# AuxTalon.net
KiCad netlist of a schematic drawn in EAGLE
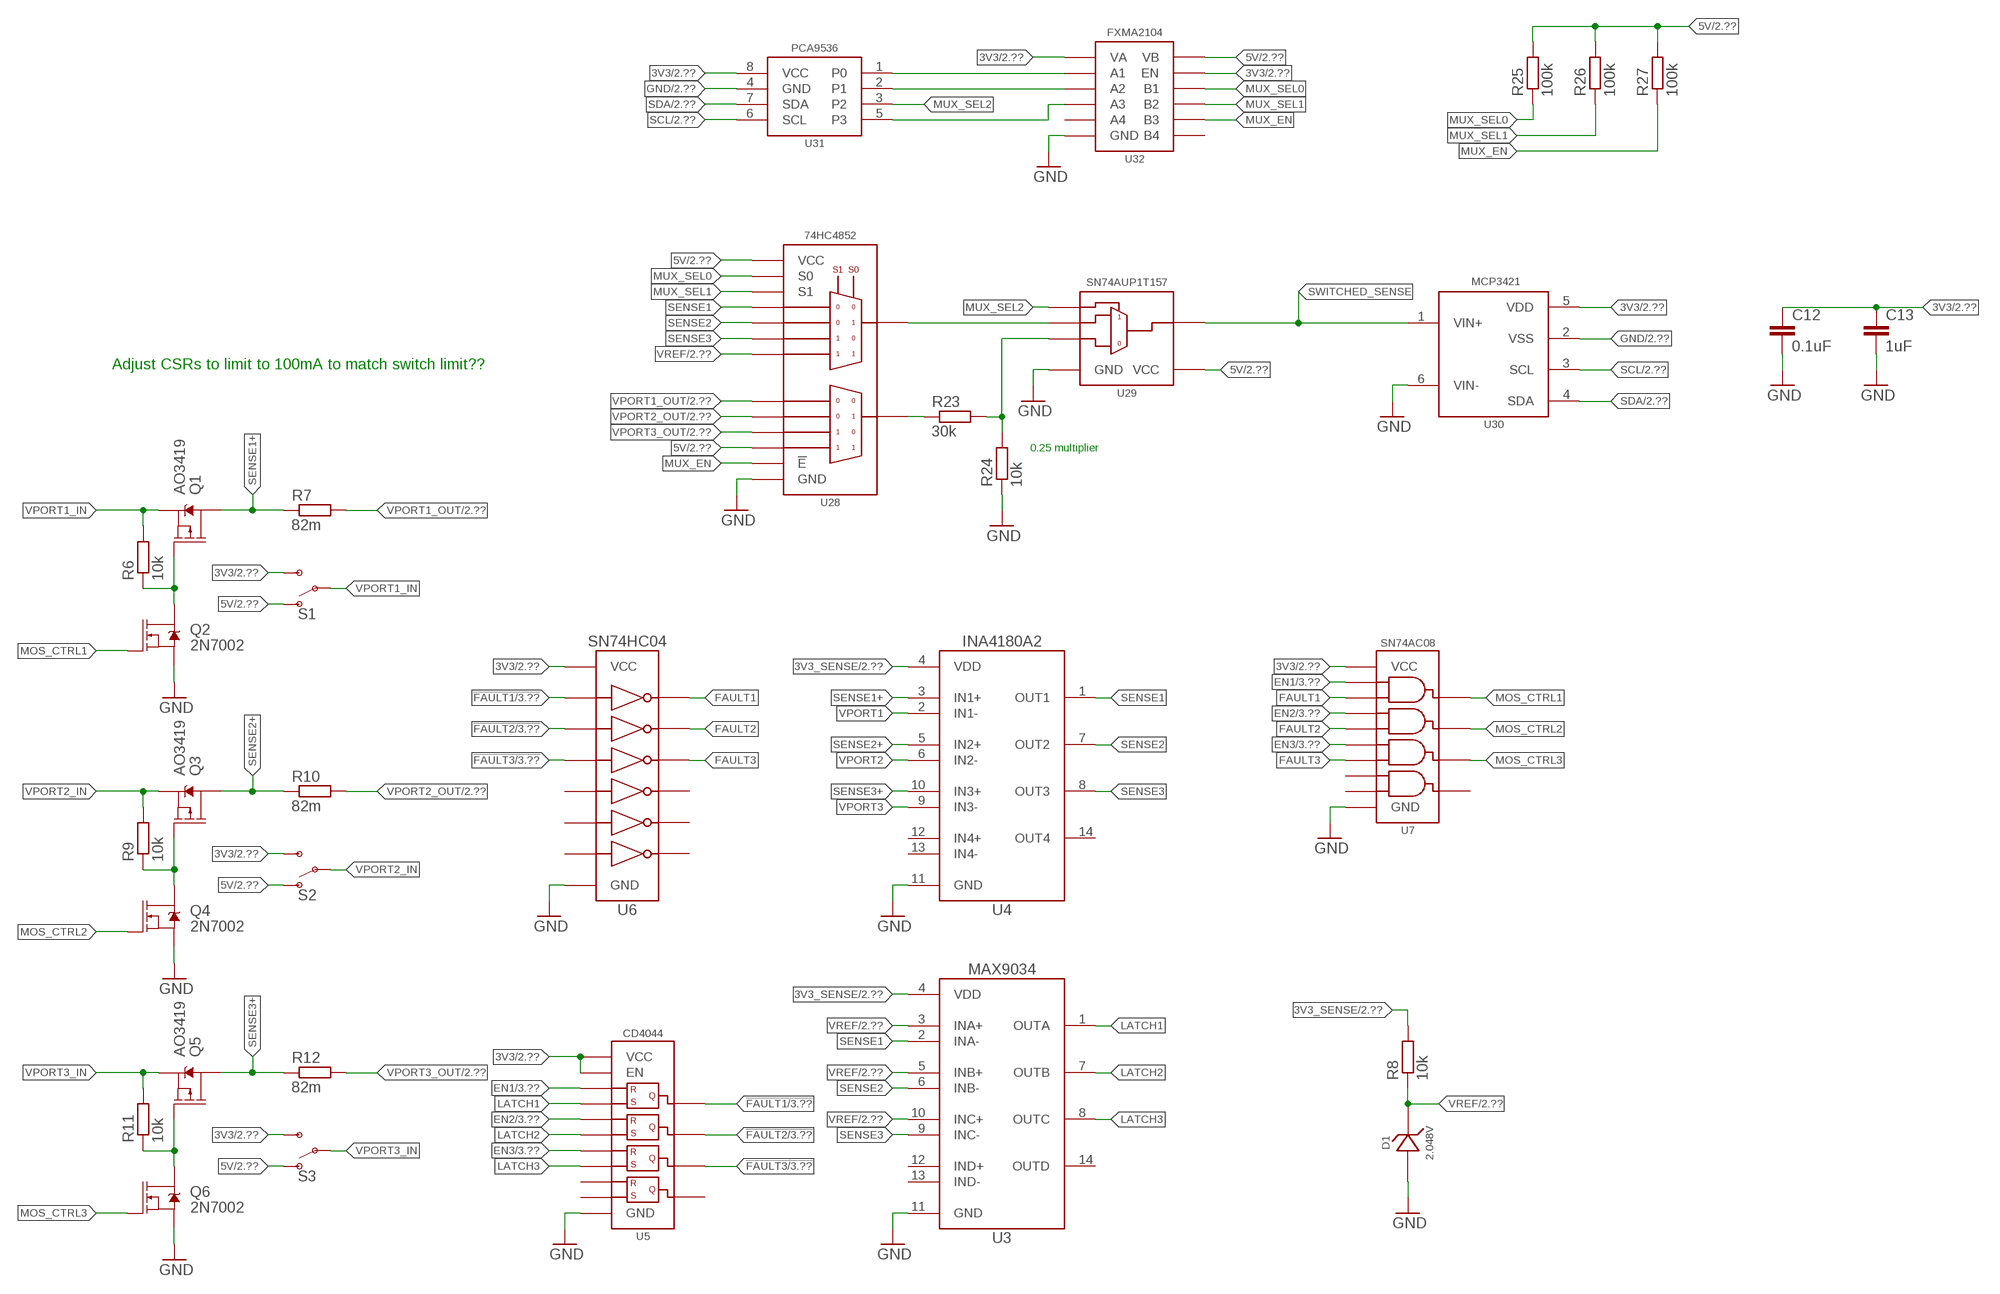
[diagram p0: schematic, sheet 1]
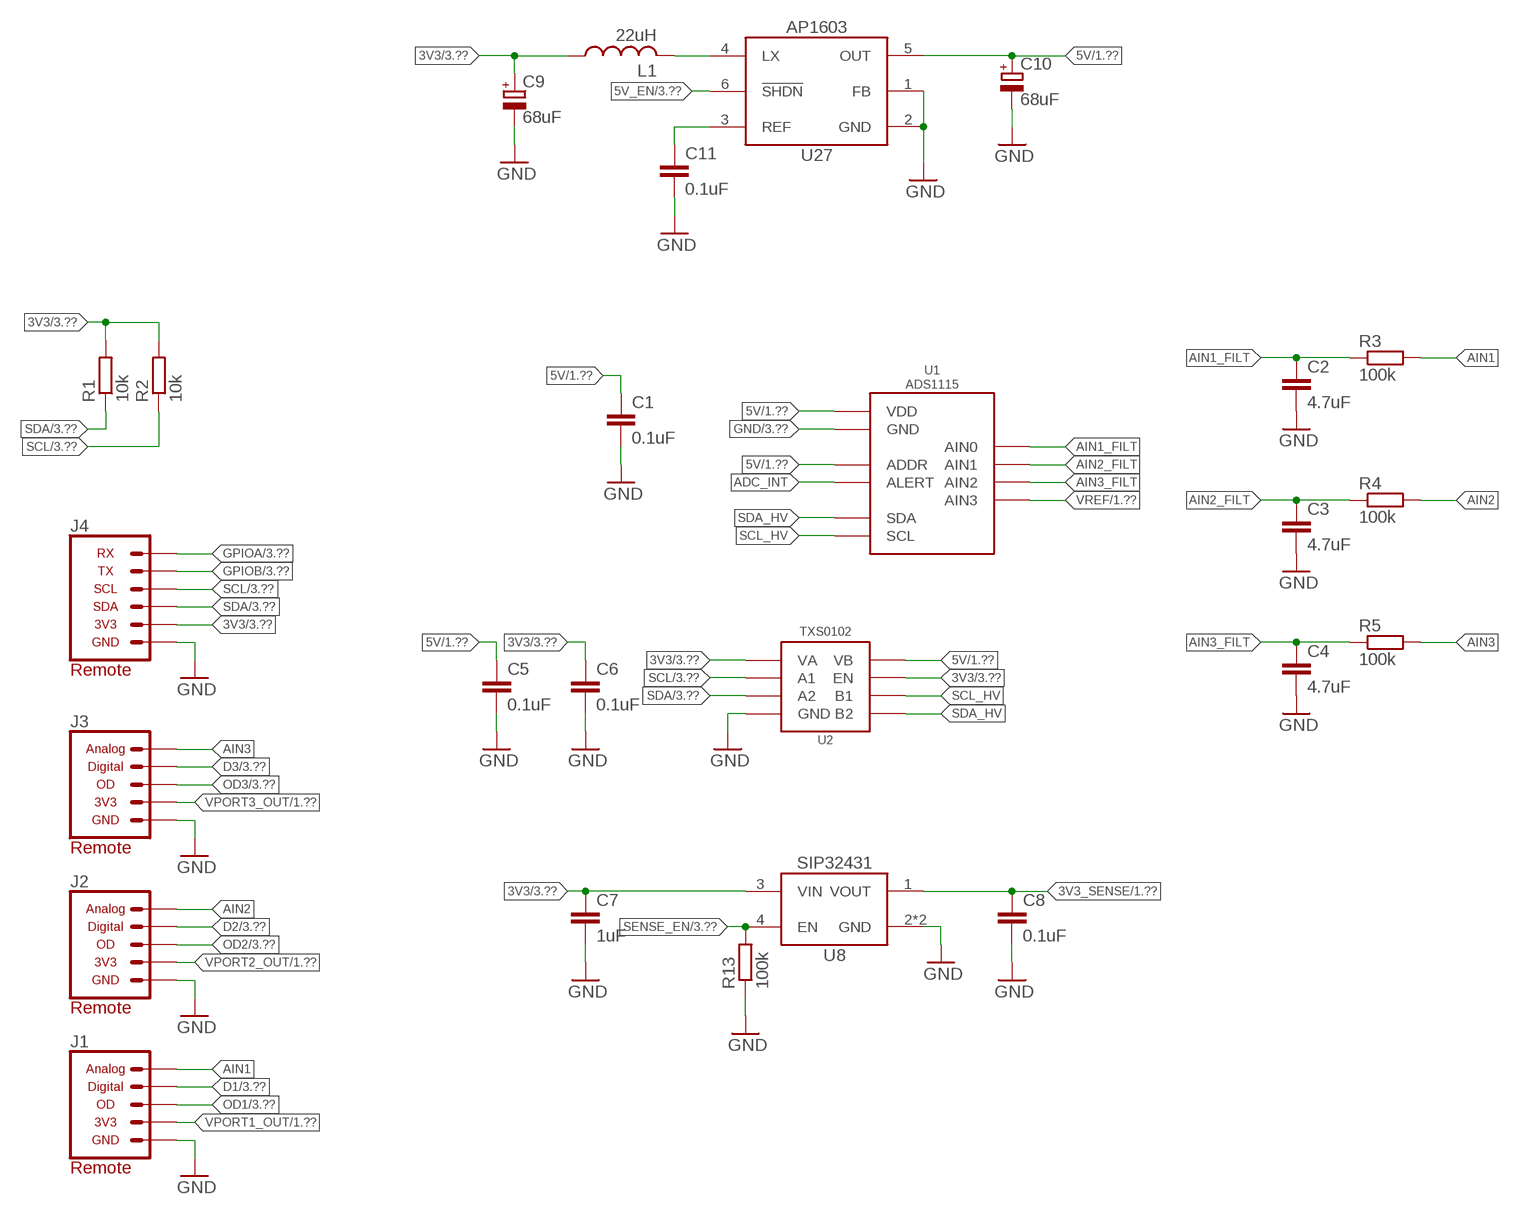
[diagram p1: schematic, sheet 2]
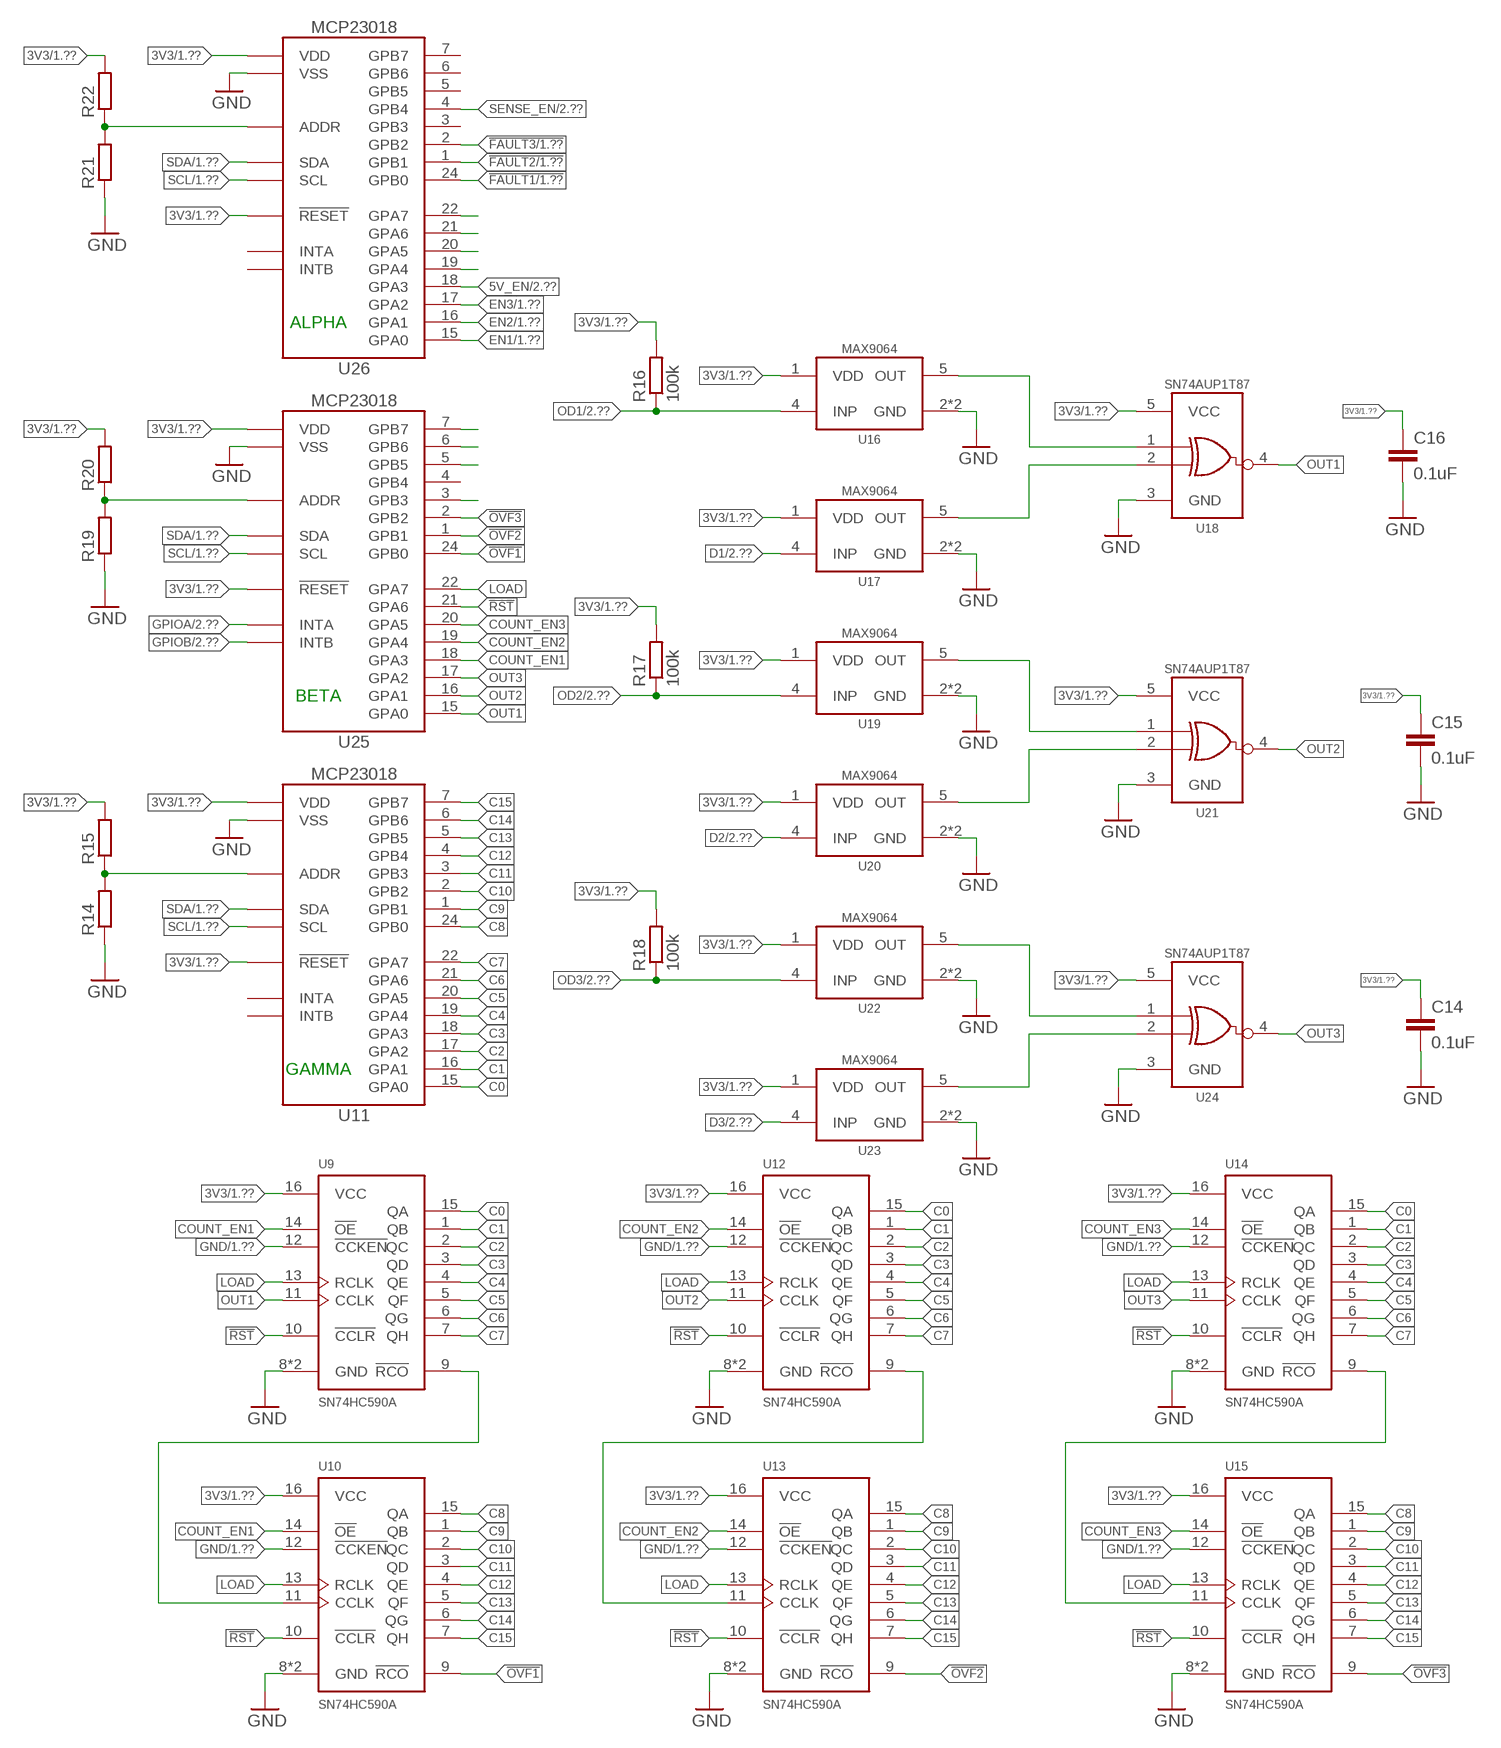
[diagram p2: schematic, sheet 3]

(export (version "E")
  (design (tool "Eeschema 10.0.6"))
  (components
    (comp (ref "C12")
      (value "0.1uF")
      (footprint "eagle-import:C0402")
      (fields (field (name "MF") "Murata") (field (name "MPN") "GCM155R71C104KA55D"))
      (libsource (lib "eagle-import") (part "C-EUC04020.1UF"))
    )
    (comp (ref "C13")
      (value "1uF")
      (footprint "eagle-import:C0805")
      (fields (field (name "MF") "Murata") (field (name "MPN") "GRM21BR61C106KE15K"))
      (libsource (lib "eagle-import") (part "C-EUC080510UF"))
    )
    (comp (ref "D1")
      (value "2.048V")
      (footprint "eagle-import:SOT23-3")
      (fields (field (name "MF") "TI") (field (name "MPN") "LM4040CIM3-2.0/NOPB"))
      (libsource (lib "eagle-import") (part "LM40402.048"))
    )
    (comp (ref "Q1")
      (value "AO3419")
      (footprint "eagle-import:SOT23-3")
      (fields (field (name "MF") "Alpha and Omega"))
      (libsource (lib "eagle-import") (part "MOSFET-PCH-AO3419"))
    )
    (comp (ref "Q2")
      (value "2N7002")
      (footprint "eagle-import:SOT23-3")
      (fields (field (name "MF") "Nexperia") (field (name "MPN") "2N7002P,215"))
      (libsource (lib "eagle-import") (part "MOSFET-NCH-2N7002P"))
    )
    (comp (ref "Q3")
      (value "AO3419")
      (footprint "eagle-import:SOT23-3")
      (fields (field (name "MF") "Alpha and Omega"))
      (libsource (lib "eagle-import") (part "MOSFET-PCH-AO3419"))
    )
    (comp (ref "Q4")
      (value "2N7002")
      (footprint "eagle-import:SOT23-3")
      (fields (field (name "MF") "Nexperia") (field (name "MPN") "2N7002P,215"))
      (libsource (lib "eagle-import") (part "MOSFET-NCH-2N7002P"))
    )
    (comp (ref "Q5")
      (value "AO3419")
      (footprint "eagle-import:SOT23-3")
      (fields (field (name "MF") "Alpha and Omega"))
      (libsource (lib "eagle-import") (part "MOSFET-PCH-AO3419"))
    )
    (comp (ref "Q6")
      (value "2N7002")
      (footprint "eagle-import:SOT23-3")
      (fields (field (name "MF") "Nexperia") (field (name "MPN") "2N7002P,215"))
      (libsource (lib "eagle-import") (part "MOSFET-NCH-2N7002P"))
    )
    (comp (ref "R6")
      (value "10k")
      (footprint "eagle-import:R0402")
      (fields (field (name "MF") "Yageo") (field (name "MPN") "RC0402FR-0710KL"))
      (libsource (lib "eagle-import") (part "R-EU_R040210K"))
    )
    (comp (ref "R7")
      (value "82m")
      (footprint "eagle-import:R0603")
      (fields (field (name "MF") "Yageo"))
      (libsource (lib "eagle-import") (part "R-EU_R0603"))
    )
    (comp (ref "R8")
      (value "10k")
      (footprint "eagle-import:R0402")
      (fields (field (name "MF") "Yageo") (field (name "MPN") "RC0402FR-0710KL"))
      (libsource (lib "eagle-import") (part "R-EU_R040210K"))
    )
    (comp (ref "R9")
      (value "10k")
      (footprint "eagle-import:R0402")
      (fields (field (name "MF") "Yageo") (field (name "MPN") "RC0402FR-0710KL"))
      (libsource (lib "eagle-import") (part "R-EU_R040210K"))
    )
    (comp (ref "R10")
      (value "82m")
      (footprint "eagle-import:R0603")
      (fields (field (name "MF") "Yageo"))
      (libsource (lib "eagle-import") (part "R-EU_R0603"))
    )
    (comp (ref "R11")
      (value "10k")
      (footprint "eagle-import:R0402")
      (fields (field (name "MF") "Yageo") (field (name "MPN") "RC0402FR-0710KL"))
      (libsource (lib "eagle-import") (part "R-EU_R040210K"))
    )
    (comp (ref "R12")
      (value "82m")
      (footprint "eagle-import:R0603")
      (fields (field (name "MF") "Yageo"))
      (libsource (lib "eagle-import") (part "R-EU_R0603"))
    )
    (comp (ref "R23")
      (value "30k")
      (footprint "eagle-import:R0402")
      (fields (field (name "MF") "Yageo"))
      (libsource (lib "eagle-import") (part "R-EU_R0402"))
    )
    (comp (ref "R24")
      (value "10k")
      (footprint "eagle-import:R0402")
      (fields (field (name "MF") "Yageo") (field (name "MPN") "RC0402FR-0710KL"))
      (libsource (lib "eagle-import") (part "R-EU_R040210K"))
    )
    (comp (ref "R25")
      (value "100k")
      (footprint "eagle-import:R0402")
      (fields (field (name "MF") "Yageo") (field (name "MPN") "RC0402FR-07100KL"))
      (libsource (lib "eagle-import") (part "R-EU_R0402100K"))
    )
    (comp (ref "R26")
      (value "100k")
      (footprint "eagle-import:R0402")
      (fields (field (name "MF") "Yageo") (field (name "MPN") "RC0402FR-07100KL"))
      (libsource (lib "eagle-import") (part "R-EU_R0402100K"))
    )
    (comp (ref "R27")
      (value "100k")
      (footprint "eagle-import:R0402")
      (fields (field (name "MF") "Yageo") (field (name "MPN") "RC0402FR-07100KL"))
      (libsource (lib "eagle-import") (part "R-EU_R0402100K"))
    )
    (comp (ref "S1")
      (value "SPDTCAS-120A1")
      (footprint "eagle-import:CAS-120A1")
      (fields (field (name "MF") "Nidec Copal") (field (name "MPN") "CAS-120TA"))
      (libsource (lib "eagle-import") (part "SPDTCAS-120A1"))
    )
    (comp (ref "S2")
      (value "SPDTCAS-120A1")
      (footprint "eagle-import:CAS-120A1")
      (fields (field (name "MF") "Nidec Copal") (field (name "MPN") "CAS-120TA"))
      (libsource (lib "eagle-import") (part "SPDTCAS-120A1"))
    )
    (comp (ref "S3")
      (value "SPDTCAS-120A1")
      (footprint "eagle-import:CAS-120A1")
      (fields (field (name "MF") "Nidec Copal") (field (name "MPN") "CAS-120TA"))
      (libsource (lib "eagle-import") (part "SPDTCAS-120A1"))
    )
    (comp (ref "U3")
      (value "MAX9034TSSOP")
      (footprint "eagle-import:TSSOP14")
      (fields (field (name "DISP") "MAX9034") (field (name "MF") "Maxim") (field (name "MPN") "MAX9034AUD+T"))
      (libsource (lib "eagle-import") (part "MAX9034TSSOP"))
    )
    (comp (ref "U4")
      (value "INA4180A2")
      (footprint "eagle-import:TSSOP14")
      (fields (field (name "DISP") "INA4180A2") (field (name "MF") "TI") (field (name "MPN") "INA4180A2IPWR"))
      (libsource (lib "eagle-import") (part "INA4180A2"))
    )
    (comp (ref "U5")
      (value "CD4044")
      (footprint "eagle-import:TSSOP16")
      (fields (field (name "DISP") "CD4044") (field (name "MF") "TI") (field (name "MPN") "CD4044BPWR"))
      (libsource (lib "eagle-import") (part "CD4044"))
    )
    (comp (ref "U6")
      (value "SN74HC04")
      (footprint "eagle-import:TSSOP14")
      (fields (field (name "MF") "TI") (field (name "MPN") "SN74HC04PWR"))
      (libsource (lib "eagle-import") (part "SN74HC04"))
    )
    (comp (ref "U7")
      (value "SN74AC08")
      (footprint "eagle-import:TSSOP14")
      (fields (field (name "MF") "TI") (field (name "MPN") "SN74AC08PWR"))
      (libsource (lib "eagle-import") (part "SN74AC08"))
    )
    (comp (ref "U28")
      (value "74HC4852")
      (footprint "eagle-import:VQFN-16")
      (fields
        (field (name "DISP") "74HC4852")
        (field (name "MF") "Nexperia")
        (field (name "MPN") "74HC4852BQ-Q100,11")
      )
      (libsource (lib "eagle-import") (part "74HC4852"))
    )
    (comp (ref "U29")
      (value "SN74AUP1T157DCK")
      (footprint "eagle-import:DCK_R-PDSO-G6")
      (fields
        (field (name "DISP") "SN74AUP1T157")
        (field (name "MF") "TI")
        (field (name "MPN") "SN74AUP1T157DCKR")
      )
      (libsource (lib "eagle-import") (part "SN74AUP1T157DCK"))
    )
    (comp (ref "U30")
      (value "MCP3421A3")
      (footprint "eagle-import:SOT23-6L")
      (fields
        (field (name "DISP") "MCP3421")
        (field (name "MF") "Microchip")
        (field (name "MPN") "MCP3421A3T-E/CH")
      )
      (libsource (lib "eagle-import") (part "MCP3421A3"))
    )
    (comp (ref "U31")
      (value "PCA9536DFN")
      (footprint "eagle-import:DFN_8_3X3")
      (fields (field (name "MF") "NXP") (field (name "MPN") "PCA9536TK,118"))
      (libsource (lib "eagle-import") (part "PCA9536DFN"))
    )
    (comp (ref "U32")
      (value "FXMA2104")
      (footprint "eagle-import:MLP_12")
      (fields
        (field (name "DISP") "FXMA2104")
        (field (name "MF") "OnSemi")
        (field (name "MPN") "FXMA2104UMX")
      )
      (libsource (lib "eagle-import") (part "FXMA2104"))
    )
    (comp (ref "C1")
      (value "0.1uF")
      (footprint "eagle-import:C0402")
      (fields (field (name "MF") "Murata") (field (name "MPN") "GCM155R71C104KA55D"))
      (libsource (lib "eagle-import") (part "C-EUC04020.1UF"))
    )
    (comp (ref "C2")
      (value "4.7uF")
      (footprint "eagle-import:C0805")
      (fields (field (name "MF") "Kemet") (field (name "MPN") "C0805C475K4RACTU"))
      (libsource (lib "eagle-import") (part "C-EUC08054.7UF"))
    )
    (comp (ref "C3")
      (value "4.7uF")
      (footprint "eagle-import:C0805")
      (fields (field (name "MF") "Kemet") (field (name "MPN") "C0805C475K4RACTU"))
      (libsource (lib "eagle-import") (part "C-EUC08054.7UF"))
    )
    (comp (ref "C4")
      (value "4.7uF")
      (footprint "eagle-import:C0805")
      (fields (field (name "MF") "Kemet") (field (name "MPN") "C0805C475K4RACTU"))
      (libsource (lib "eagle-import") (part "C-EUC08054.7UF"))
    )
    (comp (ref "C5")
      (value "0.1uF")
      (footprint "eagle-import:C0402")
      (fields (field (name "MF") "Murata") (field (name "MPN") "GCM155R71C104KA55D"))
      (libsource (lib "eagle-import") (part "C-EUC04020.1UF"))
    )
    (comp (ref "C6")
      (value "0.1uF")
      (footprint "eagle-import:C0402")
      (fields (field (name "MF") "Murata") (field (name "MPN") "GCM155R71C104KA55D"))
      (libsource (lib "eagle-import") (part "C-EUC04020.1UF"))
    )
    (comp (ref "C7")
      (value "1uF")
      (footprint "eagle-import:C0603")
      (fields (field (name "MF") "Yaiyo Yuden") (field (name "MPN") "EMK107BJ105KA-T"))
      (libsource (lib "eagle-import") (part "C-EUC06031UF"))
    )
    (comp (ref "C8")
      (value "0.1uF")
      (footprint "eagle-import:C0402")
      (fields (field (name "MF") "Murata") (field (name "MPN") "GCM155R71C104KA55D"))
      (libsource (lib "eagle-import") (part "C-EUC04020.1UF"))
    )
    (comp (ref "C9")
      (value "68uF")
      (footprint "eagle-import:153CLV-0605")
      (libsource (lib "eagle-import") (part "CPOL-EU153CLV-0605"))
    )
    (comp (ref "C10")
      (value "68uF")
      (footprint "eagle-import:153CLV-0605")
      (libsource (lib "eagle-import") (part "CPOL-EU153CLV-0605"))
    )
    (comp (ref "C11")
      (value "0.1uF")
      (footprint "eagle-import:C0402")
      (fields (field (name "MF") "Murata") (field (name "MPN") "GCM155R71C104KA55D"))
      (libsource (lib "eagle-import") (part "C-EUC04020.1UF"))
    )
    (comp (ref "J1")
      (value "CONN_AUX_M12_REMOTE")
      (footprint "eagle-import:1X05_M12_TE_T41410")
      (fields (field (name "DISP") "Remote") (field (name "MF") "TE") (field (name "MPN") "T4141012051-000"))
      (libsource (lib "eagle-import") (part "CONN_AUX_M12_REMOTE"))
    )
    (comp (ref "J2")
      (value "CONN_AUX_M12_REMOTE")
      (footprint "eagle-import:1X05_M12_TE_T41410")
      (fields (field (name "DISP") "Remote") (field (name "MF") "TE") (field (name "MPN") "T4141012051-000"))
      (libsource (lib "eagle-import") (part "CONN_AUX_M12_REMOTE"))
    )
    (comp (ref "J3")
      (value "CONN_AUX_M12_REMOTE")
      (footprint "eagle-import:1X05_M12_TE_T41410")
      (fields (field (name "DISP") "Remote") (field (name "MF") "TE") (field (name "MPN") "T4141012051-000"))
      (libsource (lib "eagle-import") (part "CONN_AUX_M12_REMOTE"))
    )
    (comp (ref "J4")
      (value "CONN_TALON_REMOTE")
      (footprint "eagle-import:1X06_MICROLOCKPLUS")
      (fields (field (name "DISP") "Remote"))
      (libsource (lib "eagle-import") (part "CONN_TALON_REMOTE"))
    )
    (comp (ref "L1")
      (value "22uH")
      (footprint "eagle-import:WE-TPC(3.8X3.8)")
      (libsource (lib "eagle-import") (part "INDUCTOR_TPC_3.8X3.8"))
    )
    (comp (ref "R1")
      (value "10k")
      (footprint "eagle-import:R0402")
      (fields (field (name "MF") "Yageo") (field (name "MPN") "RC0402FR-0710KL"))
      (libsource (lib "eagle-import") (part "R-EU_R040210K"))
    )
    (comp (ref "R2")
      (value "10k")
      (footprint "eagle-import:R0402")
      (fields (field (name "MF") "Yageo") (field (name "MPN") "RC0402FR-0710KL"))
      (libsource (lib "eagle-import") (part "R-EU_R040210K"))
    )
    (comp (ref "R3")
      (value "100k")
      (footprint "eagle-import:R0402")
      (fields (field (name "MF") "Yageo") (field (name "MPN") "RC0402FR-07100KL"))
      (libsource (lib "eagle-import") (part "R-EU_R0402100K"))
    )
    (comp (ref "R4")
      (value "100k")
      (footprint "eagle-import:R0402")
      (fields (field (name "MF") "Yageo") (field (name "MPN") "RC0402FR-07100KL"))
      (libsource (lib "eagle-import") (part "R-EU_R0402100K"))
    )
    (comp (ref "R5")
      (value "100k")
      (footprint "eagle-import:R0402")
      (fields (field (name "MF") "Yageo") (field (name "MPN") "RC0402FR-07100KL"))
      (libsource (lib "eagle-import") (part "R-EU_R0402100K"))
    )
    (comp (ref "R13")
      (value "100k")
      (footprint "eagle-import:R0402")
      (fields (field (name "MF") "Yageo") (field (name "MPN") "RC0402FR-07100KL"))
      (libsource (lib "eagle-import") (part "R-EU_R0402100K"))
    )
    (comp (ref "U1")
      (value "ADS1115")
      (footprint "eagle-import:VSSOP_10")
      (fields (field (name "MF") "TI") (field (name "MPN") "ADS1115IDGSR"))
      (libsource (lib "eagle-import") (part "ADS1115"))
    )
    (comp (ref "U2")
      (value "TXS0102DCU")
      (footprint "eagle-import:DCU_(R-PDSO-G8)")
      (fields (field (name "MF") "TI") (field (name "MPN") "TXS0102DCUR"))
      (libsource (lib "eagle-import") (part "TXS0102DCU"))
    )
    (comp (ref "U8")
      (value "SIP32431TDFN")
      (footprint "eagle-import:TDFN_4")
      (fields
        (field (name "DISP") "SIP32431")
        (field (name "MF") "Vishay")
        (field (name "MPN") "SIP32431DNP3-T1GE4")
      )
      (libsource (lib "eagle-import") (part "SIP3243TDFN1"))
    )
    (comp (ref "U27")
      (value "AP1603")
      (footprint "eagle-import:TSOT23-6_DDC")
      (fields (field (name "MF") "Diodes") (field (name "MPN") "AP1603WG-7"))
      (libsource (lib "eagle-import") (part "AP1603"))
    )
    (comp (ref "C14")
      (value "0.1uF")
      (footprint "eagle-import:C0402")
      (fields (field (name "MF") "Murata") (field (name "MPN") "GCM155R71C104KA55D"))
      (libsource (lib "eagle-import") (part "C-EUC04020.1UF"))
    )
    (comp (ref "C15")
      (value "0.1uF")
      (footprint "eagle-import:C0402")
      (fields (field (name "MF") "Murata") (field (name "MPN") "GCM155R71C104KA55D"))
      (libsource (lib "eagle-import") (part "C-EUC04020.1UF"))
    )
    (comp (ref "C16")
      (value "0.1uF")
      (footprint "eagle-import:C0402")
      (fields (field (name "MF") "Murata") (field (name "MPN") "GCM155R71C104KA55D"))
      (libsource (lib "eagle-import") (part "C-EUC04020.1UF"))
    )
    (comp (ref "R14")
      (value "R-EU_R0603")
      (footprint "eagle-import:R0603")
      (fields (field (name "MF") "Yageo"))
      (libsource (lib "eagle-import") (part "R-EU_R0603"))
    )
    (comp (ref "R15")
      (value "R-EU_R0603")
      (footprint "eagle-import:R0603")
      (fields (field (name "MF") "Yageo"))
      (libsource (lib "eagle-import") (part "R-EU_R0603"))
    )
    (comp (ref "R16")
      (value "100k")
      (footprint "eagle-import:R0402")
      (fields (field (name "MF") "Yageo") (field (name "MPN") "RC0402FR-07100KL"))
      (libsource (lib "eagle-import") (part "R-EU_R0402100K"))
    )
    (comp (ref "R17")
      (value "100k")
      (footprint "eagle-import:R0402")
      (fields (field (name "MF") "Yageo") (field (name "MPN") "RC0402FR-07100KL"))
      (libsource (lib "eagle-import") (part "R-EU_R0402100K"))
    )
    (comp (ref "R18")
      (value "100k")
      (footprint "eagle-import:R0402")
      (fields (field (name "MF") "Yageo") (field (name "MPN") "RC0402FR-07100KL"))
      (libsource (lib "eagle-import") (part "R-EU_R0402100K"))
    )
    (comp (ref "R19")
      (value "R-EU_R0603")
      (footprint "eagle-import:R0603")
      (fields (field (name "MF") "Yageo"))
      (libsource (lib "eagle-import") (part "R-EU_R0603"))
    )
    (comp (ref "R20")
      (value "R-EU_R0603")
      (footprint "eagle-import:R0603")
      (fields (field (name "MF") "Yageo"))
      (libsource (lib "eagle-import") (part "R-EU_R0603"))
    )
    (comp (ref "R21")
      (value "R-EU_R0603")
      (footprint "eagle-import:R0603")
      (fields (field (name "MF") "Yageo"))
      (libsource (lib "eagle-import") (part "R-EU_R0603"))
    )
    (comp (ref "R22")
      (value "R-EU_R0603")
      (footprint "eagle-import:R0603")
      (fields (field (name "MF") "Yageo"))
      (libsource (lib "eagle-import") (part "R-EU_R0603"))
    )
    (comp (ref "U9")
      (value "SN74HC590AVQFN")
      (footprint "eagle-import:VQFN-16")
      (fields (field (name "MF") "Nexperia") (field (name "MPN") "74HC590BQ,115"))
      (libsource (lib "eagle-import") (part "SN74HC590AVQFN"))
    )
    (comp (ref "U10")
      (value "SN74HC590AVQFN")
      (footprint "eagle-import:VQFN-16")
      (fields (field (name "MF") "Nexperia") (field (name "MPN") "74HC590BQ,115"))
      (libsource (lib "eagle-import") (part "SN74HC590AVQFN"))
    )
    (comp (ref "U11")
      (value "MCP23018QFN")
      (footprint "eagle-import:QFN24")
      (fields (field (name "MF") "TI") (field (name "MPN") "MCP23018T-E/MJ"))
      (libsource (lib "eagle-import") (part "MCP23018QFN"))
    )
    (comp (ref "U12")
      (value "SN74HC590AVQFN")
      (footprint "eagle-import:VQFN-16")
      (fields (field (name "MF") "Nexperia") (field (name "MPN") "74HC590BQ,115"))
      (libsource (lib "eagle-import") (part "SN74HC590AVQFN"))
    )
    (comp (ref "U13")
      (value "SN74HC590AVQFN")
      (footprint "eagle-import:VQFN-16")
      (fields (field (name "MF") "Nexperia") (field (name "MPN") "74HC590BQ,115"))
      (libsource (lib "eagle-import") (part "SN74HC590AVQFN"))
    )
    (comp (ref "U14")
      (value "SN74HC590AVQFN")
      (footprint "eagle-import:VQFN-16")
      (fields (field (name "MF") "Nexperia") (field (name "MPN") "74HC590BQ,115"))
      (libsource (lib "eagle-import") (part "SN74HC590AVQFN"))
    )
    (comp (ref "U15")
      (value "SN74HC590AVQFN")
      (footprint "eagle-import:VQFN-16")
      (fields (field (name "MF") "Nexperia") (field (name "MPN") "74HC590BQ,115"))
      (libsource (lib "eagle-import") (part "SN74HC590AVQFN"))
    )
    (comp (ref "U16")
      (value "MAX9064")
      (footprint "eagle-import:SOT23-5")
      (fields (field (name "DISP") "MAX9064") (field (name "MF") "Maxim") (field (name "MPN") "MAX9064EUK+T"))
      (libsource (lib "eagle-import") (part "MAX9064"))
    )
    (comp (ref "U17")
      (value "MAX9064")
      (footprint "eagle-import:SOT23-5")
      (fields (field (name "DISP") "MAX9064") (field (name "MF") "Maxim") (field (name "MPN") "MAX9064EUK+T"))
      (libsource (lib "eagle-import") (part "MAX9064"))
    )
    (comp (ref "U18")
      (value "SN74AUP1T87")
      (footprint "eagle-import:DCK_R-PDSO-G5")
      (fields
        (field (name "DISP") "SN74AUP1T87")
        (field (name "MF") "TI")
        (field (name "MPN") "SN74AUP1T87DCKR")
      )
      (libsource (lib "eagle-import") (part "SN74AUP1T87"))
    )
    (comp (ref "U19")
      (value "MAX9064")
      (footprint "eagle-import:SOT23-5")
      (fields (field (name "DISP") "MAX9064") (field (name "MF") "Maxim") (field (name "MPN") "MAX9064EUK+T"))
      (libsource (lib "eagle-import") (part "MAX9064"))
    )
    (comp (ref "U20")
      (value "MAX9064")
      (footprint "eagle-import:SOT23-5")
      (fields (field (name "DISP") "MAX9064") (field (name "MF") "Maxim") (field (name "MPN") "MAX9064EUK+T"))
      (libsource (lib "eagle-import") (part "MAX9064"))
    )
    (comp (ref "U21")
      (value "SN74AUP1T87")
      (footprint "eagle-import:DCK_R-PDSO-G5")
      (fields
        (field (name "DISP") "SN74AUP1T87")
        (field (name "MF") "TI")
        (field (name "MPN") "SN74AUP1T87DCKR")
      )
      (libsource (lib "eagle-import") (part "SN74AUP1T87"))
    )
    (comp (ref "U22")
      (value "MAX9064")
      (footprint "eagle-import:SOT23-5")
      (fields (field (name "DISP") "MAX9064") (field (name "MF") "Maxim") (field (name "MPN") "MAX9064EUK+T"))
      (libsource (lib "eagle-import") (part "MAX9064"))
    )
    (comp (ref "U23")
      (value "MAX9064")
      (footprint "eagle-import:SOT23-5")
      (fields (field (name "DISP") "MAX9064") (field (name "MF") "Maxim") (field (name "MPN") "MAX9064EUK+T"))
      (libsource (lib "eagle-import") (part "MAX9064"))
    )
    (comp (ref "U24")
      (value "SN74AUP1T87")
      (footprint "eagle-import:DCK_R-PDSO-G5")
      (fields
        (field (name "DISP") "SN74AUP1T87")
        (field (name "MF") "TI")
        (field (name "MPN") "SN74AUP1T87DCKR")
      )
      (libsource (lib "eagle-import") (part "SN74AUP1T87"))
    )
    (comp (ref "U25")
      (value "MCP23018QFN")
      (footprint "eagle-import:QFN24")
      (fields (field (name "MF") "TI") (field (name "MPN") "MCP23018T-E/MJ"))
      (libsource (lib "eagle-import") (part "MCP23018QFN"))
    )
    (comp (ref "U26")
      (value "MCP23018QFN")
      (footprint "eagle-import:QFN24")
      (fields (field (name "MF") "TI") (field (name "MPN") "MCP23018T-E/MJ"))
      (libsource (lib "eagle-import") (part "MCP23018QFN"))
    )
  )
  (nets
    (net (code "1") (name "3V3") (class "Default")
      (node (ref "C12") (pin "1") (pinfunction "1_1") (pintype "passive"))
      (node (ref "C13") (pin "1") (pinfunction "1_1") (pintype "passive"))
      (node (ref "C14") (pin "1") (pinfunction "1_1") (pintype "passive"))
      (node (ref "C15") (pin "1") (pinfunction "1_1") (pintype "passive"))
      (node (ref "C16") (pin "1") (pinfunction "1_1") (pintype "passive"))
      (node (ref "C6") (pin "1") (pinfunction "1_1") (pintype "passive"))
      (node (ref "C7") (pin "1") (pinfunction "1_1") (pintype "passive"))
      (node (ref "C9") (pin "+") (pinfunction "+_+") (pintype "passive"))
      (node (ref "J4") (pin "5") (pinfunction "3V3_5") (pintype "passive"))
      (node (ref "L1") (pin "1") (pinfunction "1_1") (pintype "passive"))
      (node (ref "R1") (pin "2") (pinfunction "2_2") (pintype "passive"))
      (node (ref "R15") (pin "2") (pinfunction "2_2") (pintype "passive"))
      (node (ref "R16") (pin "2") (pinfunction "2_2") (pintype "passive"))
      (node (ref "R17") (pin "2") (pinfunction "2_2") (pintype "passive"))
      (node (ref "R18") (pin "2") (pinfunction "2_2") (pintype "passive"))
      (node (ref "R2") (pin "2") (pinfunction "2_2") (pintype "passive"))
      (node (ref "R20") (pin "2") (pinfunction "2_2") (pintype "passive"))
      (node (ref "R22") (pin "2") (pinfunction "2_2") (pintype "passive"))
      (node (ref "S1") (pin "3") (pinfunction "S_3") (pintype "passive"))
      (node (ref "S2") (pin "3") (pinfunction "S_3") (pintype "passive"))
      (node (ref "S3") (pin "3") (pinfunction "S_3") (pintype "passive"))
      (node (ref "U10") (pin "16") (pinfunction "VCC_16") (pintype "power_in"))
      (node (ref "U11") (pin "12") (pinfunction "~{RESET}_12") (pintype "input"))
      (node (ref "U11") (pin "8") (pinfunction "VDD_8") (pintype "power_in"))
      (node (ref "U12") (pin "16") (pinfunction "VCC_16") (pintype "power_in"))
      (node (ref "U13") (pin "16") (pinfunction "VCC_16") (pintype "power_in"))
      (node (ref "U14") (pin "16") (pinfunction "VCC_16") (pintype "power_in"))
      (node (ref "U15") (pin "16") (pinfunction "VCC_16") (pintype "power_in"))
      (node (ref "U16") (pin "1") (pinfunction "VDD_1") (pintype "power_in"))
      (node (ref "U17") (pin "1") (pinfunction "VDD_1") (pintype "power_in"))
      (node (ref "U18") (pin "5") (pinfunction "VCC_5") (pintype "power_in"))
      (node (ref "U19") (pin "1") (pinfunction "VDD_1") (pintype "power_in"))
      (node (ref "U2") (pin "3") (pinfunction "VA_3") (pintype "power_in"))
      (node (ref "U2") (pin "6") (pinfunction "EN_6") (pintype "input"))
      (node (ref "U20") (pin "1") (pinfunction "VDD_1") (pintype "power_in"))
      (node (ref "U21") (pin "5") (pinfunction "VCC_5") (pintype "power_in"))
      (node (ref "U22") (pin "1") (pinfunction "VDD_1") (pintype "power_in"))
      (node (ref "U23") (pin "1") (pinfunction "VDD_1") (pintype "power_in"))
      (node (ref "U24") (pin "5") (pinfunction "VCC_5") (pintype "power_in"))
      (node (ref "U25") (pin "12") (pinfunction "~{RESET}_12") (pintype "input"))
      (node (ref "U25") (pin "8") (pinfunction "VDD_8") (pintype "power_in"))
      (node (ref "U26") (pin "12") (pinfunction "~{RESET}_12") (pintype "input"))
      (node (ref "U26") (pin "8") (pinfunction "VDD_8") (pintype "power_in"))
      (node (ref "U30") (pin "5") (pinfunction "VDD_5") (pintype "passive"))
      (node (ref "U31") (pin "8") (pinfunction "VCC_8") (pintype "power_in"))
      (node (ref "U32") (pin "2") (pinfunction "VA_2") (pintype "power_in"))
      (node (ref "U32") (pin "8") (pinfunction "EN_8") (pintype "input"))
      (node (ref "U5") (pin "16") (pinfunction "VCC_16") (pintype "power_in"))
      (node (ref "U5") (pin "5") (pinfunction "EN_5") (pintype "input"))
      (node (ref "U6") (pin "14") (pinfunction "VCC_14") (pintype "power_in"))
      (node (ref "U7") (pin "14") (pinfunction "VCC_14") (pintype "power_in"))
      (node (ref "U8") (pin "3") (pinfunction "VIN_3") (pintype "power_in"))
      (node (ref "U9") (pin "16") (pinfunction "VCC_16") (pintype "power_in"))
    )
    (net (code "2") (name "3V3_SENSE") (class "Default")
      (node (ref "C8") (pin "1") (pinfunction "1_1") (pintype "passive"))
      (node (ref "R8") (pin "2") (pinfunction "2_2") (pintype "passive"))
      (node (ref "U3") (pin "4") (pinfunction "VDD_4") (pintype "power_in"))
      (node (ref "U4") (pin "4") (pinfunction "VDD_4") (pintype "power_in"))
      (node (ref "U8") (pin "1") (pinfunction "VOUT_1") (pintype "power_in"))
    )
    (net (code "3") (name "5V") (class "Default")
      (node (ref "C1") (pin "1") (pinfunction "1_1") (pintype "passive"))
      (node (ref "C10") (pin "+") (pinfunction "+_+") (pintype "passive"))
      (node (ref "C5") (pin "1") (pinfunction "1_1") (pintype "passive"))
      (node (ref "R25") (pin "2") (pinfunction "2_2") (pintype "passive"))
      (node (ref "R26") (pin "2") (pinfunction "2_2") (pintype "passive"))
      (node (ref "R27") (pin "2") (pinfunction "2_2") (pintype "passive"))
      (node (ref "S1") (pin "1") (pinfunction "O_1") (pintype "passive"))
      (node (ref "S2") (pin "1") (pinfunction "O_1") (pintype "passive"))
      (node (ref "S3") (pin "1") (pinfunction "O_1") (pintype "passive"))
      (node (ref "U1") (pin "1") (pinfunction "ADDR_1") (pintype "bidirectional"))
      (node (ref "U1") (pin "8") (pinfunction "VDD_8") (pintype "power_in"))
      (node (ref "U2") (pin "7") (pinfunction "VB_7") (pintype "power_in"))
      (node (ref "U27") (pin "5") (pinfunction "OUT_5") (pintype "power_in"))
      (node (ref "U28") (pin "16") (pinfunction "VCC_16") (pintype "power_in"))
      (node (ref "U28") (pin "4") (pinfunction "2Y3_4") (pintype "input"))
      (node (ref "U29") (pin "5") (pinfunction "VCC_5") (pintype "power_in"))
      (node (ref "U32") (pin "1") (pinfunction "VB_1") (pintype "power_in"))
    )
    (net (code "4") (name "5V_EN") (class "Default")
      (node (ref "U26") (pin "18") (pinfunction "GPA3_18") (pintype "bidirectional"))
      (node (ref "U27") (pin "6") (pinfunction "~{SHDN}_6") (pintype "input"))
    )
    (net (code "5") (name "ADC_INT") (class "Default")
      (node (ref "U1") (pin "2") (pinfunction "ALERT_2") (pintype "bidirectional"))
    )
    (net (code "6") (name "AIN1") (class "Default")
      (node (ref "J1") (pin "4") (pinfunction "ANALOG_4") (pintype "passive"))
      (node (ref "R3") (pin "2") (pinfunction "2_2") (pintype "passive"))
    )
    (net (code "7") (name "AIN1_FILT") (class "Default")
      (node (ref "C2") (pin "1") (pinfunction "1_1") (pintype "passive"))
      (node (ref "R3") (pin "1") (pinfunction "1_1") (pintype "passive"))
      (node (ref "U1") (pin "4") (pinfunction "AIN0_4") (pintype "input"))
    )
    (net (code "8") (name "AIN2") (class "Default")
      (node (ref "J2") (pin "4") (pinfunction "ANALOG_4") (pintype "passive"))
      (node (ref "R4") (pin "2") (pinfunction "2_2") (pintype "passive"))
    )
    (net (code "9") (name "AIN2_FILT") (class "Default")
      (node (ref "C3") (pin "1") (pinfunction "1_1") (pintype "passive"))
      (node (ref "R4") (pin "1") (pinfunction "1_1") (pintype "passive"))
      (node (ref "U1") (pin "5") (pinfunction "AIN1_5") (pintype "input"))
    )
    (net (code "10") (name "AIN3") (class "Default")
      (node (ref "J3") (pin "4") (pinfunction "ANALOG_4") (pintype "passive"))
      (node (ref "R5") (pin "2") (pinfunction "2_2") (pintype "passive"))
    )
    (net (code "11") (name "AIN3_FILT") (class "Default")
      (node (ref "C4") (pin "1") (pinfunction "1_1") (pintype "passive"))
      (node (ref "R5") (pin "1") (pinfunction "1_1") (pintype "passive"))
      (node (ref "U1") (pin "6") (pinfunction "AIN2_6") (pintype "input"))
    )
    (net (code "12") (name "C0") (class "Default")
      (node (ref "U11") (pin "15") (pinfunction "GPA0_15") (pintype "bidirectional"))
      (node (ref "U12") (pin "15") (pinfunction "QA_15") (pintype "output"))
      (node (ref "U14") (pin "15") (pinfunction "QA_15") (pintype "output"))
      (node (ref "U9") (pin "15") (pinfunction "QA_15") (pintype "output"))
    )
    (net (code "13") (name "C1") (class "Default")
      (node (ref "U11") (pin "16") (pinfunction "GPA1_16") (pintype "bidirectional"))
      (node (ref "U12") (pin "1") (pinfunction "QB_1") (pintype "output"))
      (node (ref "U14") (pin "1") (pinfunction "QB_1") (pintype "output"))
      (node (ref "U9") (pin "1") (pinfunction "QB_1") (pintype "output"))
    )
    (net (code "14") (name "C2") (class "Default")
      (node (ref "U11") (pin "17") (pinfunction "GPA2_17") (pintype "bidirectional"))
      (node (ref "U12") (pin "2") (pinfunction "QC_2") (pintype "output"))
      (node (ref "U14") (pin "2") (pinfunction "QC_2") (pintype "output"))
      (node (ref "U9") (pin "2") (pinfunction "QC_2") (pintype "output"))
    )
    (net (code "15") (name "C3") (class "Default")
      (node (ref "U11") (pin "18") (pinfunction "GPA3_18") (pintype "bidirectional"))
      (node (ref "U12") (pin "3") (pinfunction "QD_3") (pintype "output"))
      (node (ref "U14") (pin "3") (pinfunction "QD_3") (pintype "output"))
      (node (ref "U9") (pin "3") (pinfunction "QD_3") (pintype "output"))
    )
    (net (code "16") (name "C4") (class "Default")
      (node (ref "U11") (pin "19") (pinfunction "GPA4_19") (pintype "bidirectional"))
      (node (ref "U12") (pin "4") (pinfunction "QE_4") (pintype "output"))
      (node (ref "U14") (pin "4") (pinfunction "QE_4") (pintype "output"))
      (node (ref "U9") (pin "4") (pinfunction "QE_4") (pintype "output"))
    )
    (net (code "17") (name "C5") (class "Default")
      (node (ref "U11") (pin "20") (pinfunction "GPA5_20") (pintype "bidirectional"))
      (node (ref "U12") (pin "5") (pinfunction "QF_5") (pintype "output"))
      (node (ref "U14") (pin "5") (pinfunction "QF_5") (pintype "output"))
      (node (ref "U9") (pin "5") (pinfunction "QF_5") (pintype "output"))
    )
    (net (code "18") (name "C6") (class "Default")
      (node (ref "U11") (pin "21") (pinfunction "GPA6_21") (pintype "bidirectional"))
      (node (ref "U12") (pin "6") (pinfunction "QG_6") (pintype "output"))
      (node (ref "U14") (pin "6") (pinfunction "QG_6") (pintype "output"))
      (node (ref "U9") (pin "6") (pinfunction "QG_6") (pintype "output"))
    )
    (net (code "19") (name "C7") (class "Default")
      (node (ref "U11") (pin "22") (pinfunction "GPA7_22") (pintype "bidirectional"))
      (node (ref "U12") (pin "7") (pinfunction "QH_7") (pintype "output"))
      (node (ref "U14") (pin "7") (pinfunction "QH_7") (pintype "output"))
      (node (ref "U9") (pin "7") (pinfunction "QH_7") (pintype "output"))
    )
    (net (code "20") (name "C8") (class "Default")
      (node (ref "U10") (pin "15") (pinfunction "QA_15") (pintype "output"))
      (node (ref "U11") (pin "24") (pinfunction "GPB0_24") (pintype "bidirectional"))
      (node (ref "U13") (pin "15") (pinfunction "QA_15") (pintype "output"))
      (node (ref "U15") (pin "15") (pinfunction "QA_15") (pintype "output"))
    )
    (net (code "21") (name "C9") (class "Default")
      (node (ref "U10") (pin "1") (pinfunction "QB_1") (pintype "output"))
      (node (ref "U11") (pin "1") (pinfunction "GPB1_1") (pintype "bidirectional"))
      (node (ref "U13") (pin "1") (pinfunction "QB_1") (pintype "output"))
      (node (ref "U15") (pin "1") (pinfunction "QB_1") (pintype "output"))
    )
    (net (code "22") (name "C10") (class "Default")
      (node (ref "U10") (pin "2") (pinfunction "QC_2") (pintype "output"))
      (node (ref "U11") (pin "2") (pinfunction "GPB2_2") (pintype "bidirectional"))
      (node (ref "U13") (pin "2") (pinfunction "QC_2") (pintype "output"))
      (node (ref "U15") (pin "2") (pinfunction "QC_2") (pintype "output"))
    )
    (net (code "23") (name "C11") (class "Default")
      (node (ref "U10") (pin "3") (pinfunction "QD_3") (pintype "output"))
      (node (ref "U11") (pin "3") (pinfunction "GPB3_3") (pintype "bidirectional"))
      (node (ref "U13") (pin "3") (pinfunction "QD_3") (pintype "output"))
      (node (ref "U15") (pin "3") (pinfunction "QD_3") (pintype "output"))
    )
    (net (code "24") (name "C12") (class "Default")
      (node (ref "U10") (pin "4") (pinfunction "QE_4") (pintype "output"))
      (node (ref "U11") (pin "4") (pinfunction "GPB4_4") (pintype "bidirectional"))
      (node (ref "U13") (pin "4") (pinfunction "QE_4") (pintype "output"))
      (node (ref "U15") (pin "4") (pinfunction "QE_4") (pintype "output"))
    )
    (net (code "25") (name "C13") (class "Default")
      (node (ref "U10") (pin "5") (pinfunction "QF_5") (pintype "output"))
      (node (ref "U11") (pin "5") (pinfunction "GPB5_5") (pintype "bidirectional"))
      (node (ref "U13") (pin "5") (pinfunction "QF_5") (pintype "output"))
      (node (ref "U15") (pin "5") (pinfunction "QF_5") (pintype "output"))
    )
    (net (code "26") (name "C14") (class "Default")
      (node (ref "U10") (pin "6") (pinfunction "QG_6") (pintype "output"))
      (node (ref "U11") (pin "6") (pinfunction "GPB6_6") (pintype "bidirectional"))
      (node (ref "U13") (pin "6") (pinfunction "QG_6") (pintype "output"))
      (node (ref "U15") (pin "6") (pinfunction "QG_6") (pintype "output"))
    )
    (net (code "27") (name "C15") (class "Default")
      (node (ref "U10") (pin "7") (pinfunction "QH_7") (pintype "output"))
      (node (ref "U11") (pin "7") (pinfunction "GPB7_7") (pintype "bidirectional"))
      (node (ref "U13") (pin "7") (pinfunction "QH_7") (pintype "output"))
      (node (ref "U15") (pin "7") (pinfunction "QH_7") (pintype "output"))
    )
    (net (code "28") (name "COUNT_EN1") (class "Default")
      (node (ref "U10") (pin "14") (pinfunction "~{OE}_14") (pintype "input"))
      (node (ref "U25") (pin "18") (pinfunction "GPA3_18") (pintype "bidirectional"))
      (node (ref "U9") (pin "14") (pinfunction "~{OE}_14") (pintype "input"))
    )
    (net (code "29") (name "COUNT_EN2") (class "Default")
      (node (ref "U12") (pin "14") (pinfunction "~{OE}_14") (pintype "input"))
      (node (ref "U13") (pin "14") (pinfunction "~{OE}_14") (pintype "input"))
      (node (ref "U25") (pin "19") (pinfunction "GPA4_19") (pintype "bidirectional"))
    )
    (net (code "30") (name "COUNT_EN3") (class "Default")
      (node (ref "U14") (pin "14") (pinfunction "~{OE}_14") (pintype "input"))
      (node (ref "U15") (pin "14") (pinfunction "~{OE}_14") (pintype "input"))
      (node (ref "U25") (pin "20") (pinfunction "GPA5_20") (pintype "bidirectional"))
    )
    (net (code "31") (name "D1") (class "Default")
      (node (ref "J1") (pin "5") (pinfunction "DIGITAL_5") (pintype "passive"))
      (node (ref "U17") (pin "4") (pinfunction "INP_4") (pintype "input"))
    )
    (net (code "32") (name "D2") (class "Default")
      (node (ref "J2") (pin "5") (pinfunction "DIGITAL_5") (pintype "passive"))
      (node (ref "U20") (pin "4") (pinfunction "INP_4") (pintype "input"))
    )
    (net (code "33") (name "D3") (class "Default")
      (node (ref "J3") (pin "5") (pinfunction "DIGITAL_5") (pintype "passive"))
      (node (ref "U23") (pin "4") (pinfunction "INP_4") (pintype "input"))
    )
    (net (code "34") (name "EN1") (class "Default")
      (node (ref "U26") (pin "15") (pinfunction "GPA0_15") (pintype "bidirectional"))
      (node (ref "U5") (pin "4") (pinfunction "R1_4") (pintype "input"))
      (node (ref "U7") (pin "1") (pinfunction "A1_1") (pintype "input"))
    )
    (net (code "35") (name "EN2") (class "Default")
      (node (ref "U26") (pin "16") (pinfunction "GPA1_16") (pintype "bidirectional"))
      (node (ref "U5") (pin "6") (pinfunction "R2_6") (pintype "input"))
      (node (ref "U7") (pin "4") (pinfunction "A2_4") (pintype "input"))
    )
    (net (code "36") (name "EN3") (class "Default")
      (node (ref "U26") (pin "17") (pinfunction "GPA2_17") (pintype "bidirectional"))
      (node (ref "U5") (pin "12") (pinfunction "R3_12") (pintype "input"))
      (node (ref "U7") (pin "9") (pinfunction "A3_9") (pintype "input"))
    )
    (net (code "37") (name "FAULT1") (class "Default")
      (node (ref "U6") (pin "2") (pinfunction "Y1_2") (pintype "output"))
      (node (ref "U7") (pin "2") (pinfunction "B1_2") (pintype "input"))
    )
    (net (code "38") (name "FAULT2") (class "Default")
      (node (ref "U6") (pin "4") (pinfunction "Y2_4") (pintype "output"))
      (node (ref "U7") (pin "5") (pinfunction "B2_5") (pintype "input"))
    )
    (net (code "39") (name "FAULT3") (class "Default")
      (node (ref "U6") (pin "6") (pinfunction "Y3_6") (pintype "output"))
      (node (ref "U7") (pin "10") (pinfunction "B3_10") (pintype "input"))
    )
    (net (code "40") (name "GND") (class "Default")
      (node (ref "C1") (pin "2") (pinfunction "2_2") (pintype "passive"))
      (node (ref "C10") (pin "-") (pinfunction "-_-") (pintype "passive"))
      (node (ref "C11") (pin "2") (pinfunction "2_2") (pintype "passive"))
      (node (ref "C12") (pin "2") (pinfunction "2_2") (pintype "passive"))
      (node (ref "C13") (pin "2") (pinfunction "2_2") (pintype "passive"))
      (node (ref "C14") (pin "2") (pinfunction "2_2") (pintype "passive"))
      (node (ref "C15") (pin "2") (pinfunction "2_2") (pintype "passive"))
      (node (ref "C16") (pin "2") (pinfunction "2_2") (pintype "passive"))
      (node (ref "C2") (pin "2") (pinfunction "2_2") (pintype "passive"))
      (node (ref "C3") (pin "2") (pinfunction "2_2") (pintype "passive"))
      (node (ref "C4") (pin "2") (pinfunction "2_2") (pintype "passive"))
      (node (ref "C5") (pin "2") (pinfunction "2_2") (pintype "passive"))
      (node (ref "C6") (pin "2") (pinfunction "2_2") (pintype "passive"))
      (node (ref "C7") (pin "2") (pinfunction "2_2") (pintype "passive"))
      (node (ref "C8") (pin "2") (pinfunction "2_2") (pintype "passive"))
      (node (ref "C9") (pin "-") (pinfunction "-_-") (pintype "passive"))
      (node (ref "D1") (pin "2") (pinfunction "A_2") (pintype "power_in"))
      (node (ref "J1") (pin "3") (pinfunction "GND_3") (pintype "passive"))
      (node (ref "J2") (pin "3") (pinfunction "GND_3") (pintype "passive"))
      (node (ref "J3") (pin "3") (pinfunction "GND_3") (pintype "passive"))
      (node (ref "J4") (pin "6") (pinfunction "GND_6") (pintype "passive"))
      (node (ref "Q2") (pin "2") (pinfunction "S_2") (pintype "bidirectional"))
      (node (ref "Q4") (pin "2") (pinfunction "S_2") (pintype "bidirectional"))
      (node (ref "Q6") (pin "2") (pinfunction "S_2") (pintype "bidirectional"))
      (node (ref "R13") (pin "1") (pinfunction "1_1") (pintype "passive"))
      (node (ref "R14") (pin "1") (pinfunction "1_1") (pintype "passive"))
      (node (ref "R19") (pin "1") (pinfunction "1_1") (pintype "passive"))
      (node (ref "R21") (pin "1") (pinfunction "1_1") (pintype "passive"))
      (node (ref "R24") (pin "1") (pinfunction "1_1") (pintype "passive"))
      (node (ref "U1") (pin "3") (pinfunction "GND_3") (pintype "power_in"))
      (node (ref "U10") (pin "12") (pinfunction "~{CCKEN}_12") (pintype "input"))
      (node (ref "U10") (pin "8") (pinfunction "GND_8") (pintype "power_in"))
      (node (ref "U10") (pin "EP") (pinfunction "GND_EP") (pintype "power_in"))
      (node (ref "U11") (pin "23") (pinfunction "VSS_23") (pintype "power_in"))
      (node (ref "U11") (pin "EP") (pinfunction "VSS_EP") (pintype "power_in"))
      (node (ref "U12") (pin "12") (pinfunction "~{CCKEN}_12") (pintype "input"))
      (node (ref "U12") (pin "8") (pinfunction "GND_8") (pintype "power_in"))
      (node (ref "U12") (pin "EP") (pinfunction "GND_EP") (pintype "power_in"))
      (node (ref "U13") (pin "12") (pinfunction "~{CCKEN}_12") (pintype "input"))
      (node (ref "U13") (pin "8") (pinfunction "GND_8") (pintype "power_in"))
      (node (ref "U13") (pin "EP") (pinfunction "GND_EP") (pintype "power_in"))
      (node (ref "U14") (pin "12") (pinfunction "~{CCKEN}_12") (pintype "input"))
      (node (ref "U14") (pin "8") (pinfunction "GND_8") (pintype "power_in"))
      (node (ref "U14") (pin "EP") (pinfunction "GND_EP") (pintype "power_in"))
      (node (ref "U15") (pin "12") (pinfunction "~{CCKEN}_12") (pintype "input"))
      (node (ref "U15") (pin "8") (pinfunction "GND_8") (pintype "power_in"))
      (node (ref "U15") (pin "EP") (pinfunction "GND_EP") (pintype "power_in"))
      (node (ref "U16") (pin "2") (pinfunction "GND_2") (pintype "power_in"))
      (node (ref "U16") (pin "3") (pinfunction "GND_3") (pintype "power_in"))
      (node (ref "U17") (pin "2") (pinfunction "GND_2") (pintype "power_in"))
      (node (ref "U17") (pin "3") (pinfunction "GND_3") (pintype "power_in"))
      (node (ref "U18") (pin "3") (pinfunction "GND_3") (pintype "power_in"))
      (node (ref "U19") (pin "2") (pinfunction "GND_2") (pintype "power_in"))
      (node (ref "U19") (pin "3") (pinfunction "GND_3") (pintype "power_in"))
      (node (ref "U2") (pin "2") (pinfunction "GND_2") (pintype "power_in"))
      (node (ref "U20") (pin "2") (pinfunction "GND_2") (pintype "power_in"))
      (node (ref "U20") (pin "3") (pinfunction "GND_3") (pintype "power_in"))
      (node (ref "U21") (pin "3") (pinfunction "GND_3") (pintype "power_in"))
      (node (ref "U22") (pin "2") (pinfunction "GND_2") (pintype "power_in"))
      (node (ref "U22") (pin "3") (pinfunction "GND_3") (pintype "power_in"))
      (node (ref "U23") (pin "2") (pinfunction "GND_2") (pintype "power_in"))
      (node (ref "U23") (pin "3") (pinfunction "GND_3") (pintype "power_in"))
      (node (ref "U24") (pin "3") (pinfunction "GND_3") (pintype "power_in"))
      (node (ref "U25") (pin "23") (pinfunction "VSS_23") (pintype "power_in"))
      (node (ref "U25") (pin "EP") (pinfunction "VSS_EP") (pintype "power_in"))
      (node (ref "U26") (pin "23") (pinfunction "VSS_23") (pintype "power_in"))
      (node (ref "U26") (pin "EP") (pinfunction "VSS_EP") (pintype "power_in"))
      (node (ref "U27") (pin "1") (pinfunction "FB_1") (pintype "input"))
      (node (ref "U27") (pin "2") (pinfunction "GND_2") (pintype "power_in"))
      (node (ref "U28") (pin "8") (pinfunction "GND_8") (pintype "power_in"))
      (node (ref "U28") (pin "EP") (pinfunction "GND_EP") (pintype "power_in"))
      (node (ref "U29") (pin "2") (pinfunction "GND_2") (pintype "power_in"))
      (node (ref "U3") (pin "11") (pinfunction "GND_11") (pintype "power_in"))
      (node (ref "U30") (pin "2") (pinfunction "VSS_2") (pintype "passive"))
      (node (ref "U30") (pin "6") (pinfunction "VIN-_6") (pintype "input"))
      (node (ref "U31") (pin "4") (pinfunction "GND_4") (pintype "power_in"))
      (node (ref "U32") (pin "7") (pinfunction "GND_7") (pintype "power_in"))
      (node (ref "U4") (pin "11") (pinfunction "GND_11") (pintype "power_in"))
      (node (ref "U5") (pin "8") (pinfunction "GND_8") (pintype "power_in"))
      (node (ref "U6") (pin "7") (pinfunction "GND_7") (pintype "power_in"))
      (node (ref "U7") (pin "7") (pinfunction "GND_7") (pintype "power_in"))
      (node (ref "U8") (pin "2") (pinfunction "GND_2") (pintype "power_in"))
      (node (ref "U8") (pin "EP") (pinfunction "GND_EP") (pintype "power_in"))
      (node (ref "U9") (pin "12") (pinfunction "~{CCKEN}_12") (pintype "input"))
      (node (ref "U9") (pin "8") (pinfunction "GND_8") (pintype "power_in"))
      (node (ref "U9") (pin "EP") (pinfunction "GND_EP") (pintype "power_in"))
    )
    (net (code "41") (name "GPIOA") (class "Default")
      (node (ref "J4") (pin "1") (pinfunction "RX_1") (pintype "passive"))
      (node (ref "U25") (pin "14") (pinfunction "INTA_14") (pintype "output"))
    )
    (net (code "42") (name "GPIOB") (class "Default")
      (node (ref "J4") (pin "2") (pinfunction "TX_2") (pintype "passive"))
      (node (ref "U25") (pin "13") (pinfunction "INTB_13") (pintype "output"))
    )
    (net (code "43") (name "LATCH1") (class "Default")
      (node (ref "U3") (pin "1") (pinfunction "OUTA_1") (pintype "output"))
      (node (ref "U5") (pin "3") (pinfunction "S1_3") (pintype "input"))
    )
    (net (code "44") (name "LATCH2") (class "Default")
      (node (ref "U3") (pin "7") (pinfunction "OUTB_7") (pintype "output"))
      (node (ref "U5") (pin "7") (pinfunction "S2_7") (pintype "input"))
    )
    (net (code "45") (name "LATCH3") (class "Default")
      (node (ref "U3") (pin "8") (pinfunction "OUTC_8") (pintype "output"))
      (node (ref "U5") (pin "11") (pinfunction "S3_11") (pintype "input"))
    )
    (net (code "46") (name "LOAD") (class "Default")
      (node (ref "U10") (pin "13") (pinfunction "RCLK_13") (pintype "input"))
      (node (ref "U12") (pin "13") (pinfunction "RCLK_13") (pintype "input"))
      (node (ref "U13") (pin "13") (pinfunction "RCLK_13") (pintype "input"))
      (node (ref "U14") (pin "13") (pinfunction "RCLK_13") (pintype "input"))
      (node (ref "U15") (pin "13") (pinfunction "RCLK_13") (pintype "input"))
      (node (ref "U25") (pin "22") (pinfunction "GPA7_22") (pintype "bidirectional"))
      (node (ref "U9") (pin "13") (pinfunction "RCLK_13") (pintype "input"))
    )
    (net (code "47") (name "MOS_CTRL1") (class "Default")
      (node (ref "Q2") (pin "1") (pinfunction "G_1") (pintype "bidirectional"))
      (node (ref "U7") (pin "3") (pinfunction "Y1_3") (pintype "output"))
    )
    (net (code "48") (name "MOS_CTRL2") (class "Default")
      (node (ref "Q4") (pin "1") (pinfunction "G_1") (pintype "bidirectional"))
      (node (ref "U7") (pin "6") (pinfunction "Y2_6") (pintype "output"))
    )
    (net (code "49") (name "MOS_CTRL3") (class "Default")
      (node (ref "Q6") (pin "1") (pinfunction "G_1") (pintype "bidirectional"))
      (node (ref "U7") (pin "8") (pinfunction "Y3_8") (pintype "output"))
    )
    (net (code "50") (name "MUX_EN") (class "Default")
      (node (ref "R27") (pin "1") (pinfunction "1_1") (pintype "passive"))
      (node (ref "U28") (pin "6") (pinfunction "~{E}_6") (pintype "input"))
      (node (ref "U32") (pin "10") (pinfunction "B3_10") (pintype "bidirectional"))
    )
    (net (code "51") (name "MUX_SEL0") (class "Default")
      (node (ref "R25") (pin "1") (pinfunction "1_1") (pintype "passive"))
      (node (ref "U28") (pin "10") (pinfunction "S0_10") (pintype "input"))
      (node (ref "U32") (pin "12") (pinfunction "B1_12") (pintype "bidirectional"))
    )
    (net (code "52") (name "MUX_SEL1") (class "Default")
      (node (ref "R26") (pin "1") (pinfunction "1_1") (pintype "passive"))
      (node (ref "U28") (pin "9") (pinfunction "S1_9") (pintype "input"))
      (node (ref "U32") (pin "11") (pinfunction "B2_11") (pintype "bidirectional"))
    )
    (net (code "53") (name "MUX_SEL2") (class "Default")
      (node (ref "U25") (pin "5") (pinfunction "GPB5_5") (pintype "bidirectional"))
      (node (ref "U29") (pin "4") (pinfunction "C_4") (pintype "input"))
      (node (ref "U31") (pin "3") (pinfunction "P2_3") (pintype "bidirectional"))
    )
    (net (code "54") (name "Net-(Q1-G)") (class "Default")
      (node (ref "Q1") (pin "1") (pinfunction "G_1") (pintype "bidirectional"))
      (node (ref "Q2") (pin "3") (pinfunction "D_3") (pintype "bidirectional"))
      (node (ref "R6") (pin "1") (pinfunction "1_1") (pintype "passive"))
    )
    (net (code "55") (name "Net-(Q3-G)") (class "Default")
      (node (ref "Q3") (pin "1") (pinfunction "G_1") (pintype "bidirectional"))
      (node (ref "Q4") (pin "3") (pinfunction "D_3") (pintype "bidirectional"))
      (node (ref "R9") (pin "1") (pinfunction "1_1") (pintype "passive"))
    )
    (net (code "56") (name "Net-(Q5-G)") (class "Default")
      (node (ref "Q5") (pin "1") (pinfunction "G_1") (pintype "bidirectional"))
      (node (ref "Q6") (pin "3") (pinfunction "D_3") (pintype "bidirectional"))
      (node (ref "R11") (pin "1") (pinfunction "1_1") (pintype "passive"))
    )
    (net (code "57") (name "Net-(U10-CCLK)") (class "Default")
      (node (ref "U10") (pin "11") (pinfunction "CCLK_11") (pintype "input"))
      (node (ref "U9") (pin "9") (pinfunction "~{RCO}_9") (pintype "output"))
    )
    (net (code "58") (name "Net-(U11-ADDR)") (class "Default")
      (node (ref "R14") (pin "2") (pinfunction "2_2") (pintype "passive"))
      (node (ref "R15") (pin "1") (pinfunction "1_1") (pintype "passive"))
      (node (ref "U11") (pin "11") (pinfunction "ADDR_11") (pintype "input"))
    )
    (net (code "59") (name "Net-(U12-~{RCO})") (class "Default")
      (node (ref "U12") (pin "9") (pinfunction "~{RCO}_9") (pintype "output"))
      (node (ref "U13") (pin "11") (pinfunction "CCLK_11") (pintype "input"))
    )
    (net (code "60") (name "Net-(U14-~{RCO})") (class "Default")
      (node (ref "U14") (pin "9") (pinfunction "~{RCO}_9") (pintype "output"))
      (node (ref "U15") (pin "11") (pinfunction "CCLK_11") (pintype "input"))
    )
    (net (code "61") (name "Net-(U16-OUT)") (class "Default")
      (node (ref "U16") (pin "5") (pinfunction "OUT_5") (pintype "output"))
      (node (ref "U18") (pin "1") (pinfunction "A_1") (pintype "input"))
    )
    (net (code "62") (name "Net-(U17-OUT)") (class "Default")
      (node (ref "U17") (pin "5") (pinfunction "OUT_5") (pintype "output"))
      (node (ref "U18") (pin "2") (pinfunction "B_2") (pintype "input"))
    )
    (net (code "63") (name "Net-(U19-OUT)") (class "Default")
      (node (ref "U19") (pin "5") (pinfunction "OUT_5") (pintype "output"))
      (node (ref "U21") (pin "1") (pinfunction "A_1") (pintype "input"))
    )
    (net (code "64") (name "Net-(U20-OUT)") (class "Default")
      (node (ref "U20") (pin "5") (pinfunction "OUT_5") (pintype "output"))
      (node (ref "U21") (pin "2") (pinfunction "B_2") (pintype "input"))
    )
    (net (code "65") (name "Net-(U22-OUT)") (class "Default")
      (node (ref "U22") (pin "5") (pinfunction "OUT_5") (pintype "output"))
      (node (ref "U24") (pin "1") (pinfunction "A_1") (pintype "input"))
    )
    (net (code "66") (name "Net-(U23-OUT)") (class "Default")
      (node (ref "U23") (pin "5") (pinfunction "OUT_5") (pintype "output"))
      (node (ref "U24") (pin "2") (pinfunction "B_2") (pintype "input"))
    )
    (net (code "67") (name "Net-(U25-ADDR)") (class "Default")
      (node (ref "R19") (pin "2") (pinfunction "2_2") (pintype "passive"))
      (node (ref "R20") (pin "1") (pinfunction "1_1") (pintype "passive"))
      (node (ref "U25") (pin "11") (pinfunction "ADDR_11") (pintype "input"))
    )
    (net (code "68") (name "Net-(U26-ADDR)") (class "Default")
      (node (ref "R21") (pin "2") (pinfunction "2_2") (pintype "passive"))
      (node (ref "R22") (pin "1") (pinfunction "1_1") (pintype "passive"))
      (node (ref "U26") (pin "11") (pinfunction "ADDR_11") (pintype "input"))
    )
    (net (code "69") (name "Net-(U27-LX)") (class "Default")
      (node (ref "L1") (pin "2") (pinfunction "2_2") (pintype "passive"))
      (node (ref "U27") (pin "4") (pinfunction "LX_4") (pintype "power_in"))
    )
    (net (code "70") (name "Net-(U27-REF)") (class "Default")
      (node (ref "C11") (pin "1") (pinfunction "1_1") (pintype "passive"))
      (node (ref "U27") (pin "3") (pinfunction "REF_3") (pintype "passive"))
    )
    (net (code "71") (name "Net-(U28-1Z)") (class "Default")
      (node (ref "U28") (pin "13") (pinfunction "1Z_13") (pintype "output"))
      (node (ref "U29") (pin "1") (pinfunction "A_1") (pintype "input"))
    )
    (net (code "72") (name "Net-(U28-2Z)") (class "Default")
      (node (ref "R23") (pin "1") (pinfunction "1_1") (pintype "passive"))
      (node (ref "U28") (pin "3") (pinfunction "2Z_3") (pintype "output"))
    )
    (net (code "73") (name "Net-(U29-B)") (class "Default")
      (node (ref "R23") (pin "2") (pinfunction "2_2") (pintype "passive"))
      (node (ref "R24") (pin "2") (pinfunction "2_2") (pintype "passive"))
      (node (ref "U29") (pin "3") (pinfunction "B_3") (pintype "input"))
    )
    (net (code "74") (name "Net-(U31-P0)") (class "Default")
      (node (ref "U31") (pin "1") (pinfunction "P0_1") (pintype "bidirectional"))
      (node (ref "U32") (pin "3") (pinfunction "A1_3") (pintype "bidirectional"))
    )
    (net (code "75") (name "Net-(U31-P1)") (class "Default")
      (node (ref "U31") (pin "2") (pinfunction "P1_2") (pintype "bidirectional"))
      (node (ref "U32") (pin "4") (pinfunction "A2_4") (pintype "bidirectional"))
    )
    (net (code "76") (name "Net-(U31-P3)") (class "Default")
      (node (ref "U31") (pin "5") (pinfunction "P3_5") (pintype "bidirectional"))
      (node (ref "U32") (pin "5") (pinfunction "A3_5") (pintype "bidirectional"))
    )
    (net (code "77") (name "OD1") (class "Default")
      (node (ref "J1") (pin "2") (pinfunction "DIGITAL_OPENDRAIN_2") (pintype "passive"))
      (node (ref "R16") (pin "1") (pinfunction "1_1") (pintype "passive"))
      (node (ref "U16") (pin "4") (pinfunction "INP_4") (pintype "input"))
    )
    (net (code "78") (name "OD2") (class "Default")
      (node (ref "J2") (pin "2") (pinfunction "DIGITAL_OPENDRAIN_2") (pintype "passive"))
      (node (ref "R17") (pin "1") (pinfunction "1_1") (pintype "passive"))
      (node (ref "U19") (pin "4") (pinfunction "INP_4") (pintype "input"))
    )
    (net (code "79") (name "OD3") (class "Default")
      (node (ref "J3") (pin "2") (pinfunction "DIGITAL_OPENDRAIN_2") (pintype "passive"))
      (node (ref "R18") (pin "1") (pinfunction "1_1") (pintype "passive"))
      (node (ref "U22") (pin "4") (pinfunction "INP_4") (pintype "input"))
    )
    (net (code "80") (name "OUT1") (class "Default")
      (node (ref "U18") (pin "4") (pinfunction "Y_4") (pintype "output"))
      (node (ref "U25") (pin "15") (pinfunction "GPA0_15") (pintype "bidirectional"))
      (node (ref "U9") (pin "11") (pinfunction "CCLK_11") (pintype "input"))
    )
    (net (code "81") (name "OUT2") (class "Default")
      (node (ref "U12") (pin "11") (pinfunction "CCLK_11") (pintype "input"))
      (node (ref "U21") (pin "4") (pinfunction "Y_4") (pintype "output"))
      (node (ref "U25") (pin "16") (pinfunction "GPA1_16") (pintype "bidirectional"))
    )
    (net (code "82") (name "OUT3") (class "Default")
      (node (ref "U14") (pin "11") (pinfunction "CCLK_11") (pintype "input"))
      (node (ref "U24") (pin "4") (pinfunction "Y_4") (pintype "output"))
      (node (ref "U25") (pin "17") (pinfunction "GPA2_17") (pintype "bidirectional"))
    )
    (net (code "83") (name "SCL") (class "Default")
      (node (ref "J4") (pin "3") (pinfunction "SCL_3") (pintype "passive"))
      (node (ref "R2") (pin "1") (pinfunction "1_1") (pintype "passive"))
      (node (ref "U11") (pin "9") (pinfunction "SCL_9") (pintype "input"))
      (node (ref "U2") (pin "5") (pinfunction "A1_5") (pintype "bidirectional"))
      (node (ref "U25") (pin "9") (pinfunction "SCL_9") (pintype "input"))
      (node (ref "U26") (pin "9") (pinfunction "SCL_9") (pintype "input"))
      (node (ref "U30") (pin "3") (pinfunction "SCL_3") (pintype "bidirectional"))
      (node (ref "U31") (pin "6") (pinfunction "SCL_6") (pintype "input"))
    )
    (net (code "84") (name "SCL_HV") (class "Default")
      (node (ref "U1") (pin "10") (pinfunction "SCL_10") (pintype "input"))
      (node (ref "U2") (pin "8") (pinfunction "B1_8") (pintype "bidirectional"))
    )
    (net (code "85") (name "SDA") (class "Default")
      (node (ref "J4") (pin "4") (pinfunction "SDA_4") (pintype "passive"))
      (node (ref "R1") (pin "1") (pinfunction "1_1") (pintype "passive"))
      (node (ref "U11") (pin "10") (pinfunction "SDA_10") (pintype "bidirectional"))
      (node (ref "U2") (pin "4") (pinfunction "A2_4") (pintype "bidirectional"))
      (node (ref "U25") (pin "10") (pinfunction "SDA_10") (pintype "bidirectional"))
      (node (ref "U26") (pin "10") (pinfunction "SDA_10") (pintype "bidirectional"))
      (node (ref "U30") (pin "4") (pinfunction "SDA_4") (pintype "bidirectional"))
      (node (ref "U31") (pin "7") (pinfunction "SDA_7") (pintype "bidirectional"))
    )
    (net (code "86") (name "SDA_HV") (class "Default")
      (node (ref "U1") (pin "9") (pinfunction "SDA_9") (pintype "bidirectional"))
      (node (ref "U2") (pin "1") (pinfunction "B2_1") (pintype "bidirectional"))
    )
    (net (code "87") (name "SENSE1") (class "Default")
      (node (ref "U28") (pin "12") (pinfunction "1Y0_12") (pintype "input"))
      (node (ref "U3") (pin "2") (pinfunction "INA-_2") (pintype "input"))
      (node (ref "U4") (pin "1") (pinfunction "OUT1_1") (pintype "output"))
    )
    (net (code "88") (name "SENSE1+") (class "Default")
      (node (ref "Q1") (pin "3") (pinfunction "D_3") (pintype "bidirectional"))
      (node (ref "R7") (pin "1") (pinfunction "1_1") (pintype "passive"))
      (node (ref "U4") (pin "3") (pinfunction "IN1+_3") (pintype "input"))
    )
    (net (code "89") (name "SENSE2") (class "Default")
      (node (ref "U28") (pin "14") (pinfunction "1Y1_14") (pintype "input"))
      (node (ref "U3") (pin "6") (pinfunction "INB-_6") (pintype "input"))
      (node (ref "U4") (pin "7") (pinfunction "OUT2_7") (pintype "output"))
    )
    (net (code "90") (name "SENSE2+") (class "Default")
      (node (ref "Q3") (pin "3") (pinfunction "D_3") (pintype "bidirectional"))
      (node (ref "R10") (pin "1") (pinfunction "1_1") (pintype "passive"))
      (node (ref "U4") (pin "5") (pinfunction "IN2+_5") (pintype "input"))
    )
    (net (code "91") (name "SENSE3") (class "Default")
      (node (ref "U28") (pin "15") (pinfunction "1Y2_15") (pintype "input"))
      (node (ref "U3") (pin "9") (pinfunction "INC-_9") (pintype "input"))
      (node (ref "U4") (pin "8") (pinfunction "OUT3_8") (pintype "output"))
    )
    (net (code "92") (name "SENSE3+") (class "Default")
      (node (ref "Q5") (pin "3") (pinfunction "D_3") (pintype "bidirectional"))
      (node (ref "R12") (pin "1") (pinfunction "1_1") (pintype "passive"))
      (node (ref "U4") (pin "10") (pinfunction "IN3+_10") (pintype "input"))
    )
    (net (code "93") (name "SENSE_EN") (class "Default")
      (node (ref "R13") (pin "2") (pinfunction "2_2") (pintype "passive"))
      (node (ref "U26") (pin "4") (pinfunction "GPB4_4") (pintype "bidirectional"))
      (node (ref "U8") (pin "4") (pinfunction "EN_4") (pintype "input"))
    )
    (net (code "94") (name "SWITCHED_SENSE") (class "Default")
      (node (ref "U29") (pin "6") (pinfunction "Y_6") (pintype "output"))
      (node (ref "U30") (pin "1") (pinfunction "VIN+_1") (pintype "input"))
    )
    (net (code "95") (name "VPORT1") (class "Default")
      (node (ref "U4") (pin "2") (pinfunction "IN1-_2") (pintype "input"))
    )
    (net (code "96") (name "VPORT1_IN") (class "Default")
      (node (ref "Q1") (pin "2") (pinfunction "S_2") (pintype "bidirectional"))
      (node (ref "R6") (pin "2") (pinfunction "2_2") (pintype "passive"))
      (node (ref "S1") (pin "2") (pinfunction "P_2") (pintype "passive"))
    )
    (net (code "97") (name "VPORT1_OUT") (class "Default")
      (node (ref "J1") (pin "1") (pinfunction "3V3_1") (pintype "passive"))
      (node (ref "R7") (pin "2") (pinfunction "2_2") (pintype "passive"))
      (node (ref "U28") (pin "1") (pinfunction "2Y0_1") (pintype "input"))
    )
    (net (code "98") (name "VPORT2") (class "Default")
      (node (ref "U4") (pin "6") (pinfunction "IN2-_6") (pintype "input"))
    )
    (net (code "99") (name "VPORT2_IN") (class "Default")
      (node (ref "Q3") (pin "2") (pinfunction "S_2") (pintype "bidirectional"))
      (node (ref "R9") (pin "2") (pinfunction "2_2") (pintype "passive"))
      (node (ref "S2") (pin "2") (pinfunction "P_2") (pintype "passive"))
    )
    (net (code "100") (name "VPORT2_OUT") (class "Default")
      (node (ref "J2") (pin "1") (pinfunction "3V3_1") (pintype "passive"))
      (node (ref "R10") (pin "2") (pinfunction "2_2") (pintype "passive"))
      (node (ref "U28") (pin "5") (pinfunction "2Y1_5") (pintype "input"))
    )
    (net (code "101") (name "VPORT3") (class "Default")
      (node (ref "U4") (pin "9") (pinfunction "IN3-_9") (pintype "input"))
    )
    (net (code "102") (name "VPORT3_IN") (class "Default")
      (node (ref "Q5") (pin "2") (pinfunction "S_2") (pintype "bidirectional"))
      (node (ref "R11") (pin "2") (pinfunction "2_2") (pintype "passive"))
      (node (ref "S3") (pin "2") (pinfunction "P_2") (pintype "passive"))
    )
    (net (code "103") (name "VPORT3_OUT") (class "Default")
      (node (ref "J3") (pin "1") (pinfunction "3V3_1") (pintype "passive"))
      (node (ref "R12") (pin "2") (pinfunction "2_2") (pintype "passive"))
      (node (ref "U28") (pin "2") (pinfunction "2Y2_2") (pintype "input"))
    )
    (net (code "104") (name "VREF") (class "Default")
      (node (ref "D1") (pin "1") (pinfunction "C_1") (pintype "power_in"))
      (node (ref "R8") (pin "1") (pinfunction "1_1") (pintype "passive"))
      (node (ref "U1") (pin "7") (pinfunction "AIN3_7") (pintype "input"))
      (node (ref "U28") (pin "11") (pinfunction "1Y3_11") (pintype "input"))
      (node (ref "U3") (pin "10") (pinfunction "INC+_10") (pintype "input"))
      (node (ref "U3") (pin "3") (pinfunction "INA+_3") (pintype "input"))
      (node (ref "U3") (pin "5") (pinfunction "INB+_5") (pintype "input"))
    )
    (net (code "105") (name "unconnected-(U3-IND+-Pad12)") (class "Default")
      (node (ref "U3") (pin "12") (pinfunction "IND+_12") (pintype "input"))
    )
    (net (code "106") (name "unconnected-(U3-IND--Pad13)") (class "Default")
      (node (ref "U3") (pin "13") (pinfunction "IND-_13") (pintype "input"))
    )
    (net (code "107") (name "unconnected-(U3-OUTD-Pad14)") (class "Default")
      (node (ref "U3") (pin "14") (pinfunction "OUTD_14") (pintype "output"))
    )
    (net (code "108") (name "unconnected-(U4-IN4+-Pad12)") (class "Default")
      (node (ref "U4") (pin "12") (pinfunction "IN4+_12") (pintype "input"))
    )
    (net (code "109") (name "unconnected-(U4-IN4--Pad13)") (class "Default")
      (node (ref "U4") (pin "13") (pinfunction "IN4-_13") (pintype "input"))
    )
    (net (code "110") (name "unconnected-(U4-OUT4-Pad14)") (class "Default")
      (node (ref "U4") (pin "14") (pinfunction "OUT4_14") (pintype "output"))
    )
    (net (code "111") (name "unconnected-(U5-Q4-Pad1)") (class "Default")
      (node (ref "U5") (pin "1") (pinfunction "Q4_1") (pintype "output"))
    )
    (net (code "112") (name "unconnected-(U5-R4-Pad14)") (class "Default")
      (node (ref "U5") (pin "14") (pinfunction "R4_14") (pintype "input"))
    )
    (net (code "113") (name "unconnected-(U5-S4-Pad15)") (class "Default")
      (node (ref "U5") (pin "15") (pinfunction "S4_15") (pintype "input"))
    )
    (net (code "114") (name "unconnected-(U6-A4-Pad9)") (class "Default")
      (node (ref "U6") (pin "9") (pinfunction "A4_9") (pintype "input"))
    )
    (net (code "115") (name "unconnected-(U6-A5-Pad11)") (class "Default")
      (node (ref "U6") (pin "11") (pinfunction "A5_11") (pintype "input"))
    )
    (net (code "116") (name "unconnected-(U6-A6-Pad13)") (class "Default")
      (node (ref "U6") (pin "13") (pinfunction "A6_13") (pintype "input"))
    )
    (net (code "117") (name "unconnected-(U6-Y4-Pad8)") (class "Default")
      (node (ref "U6") (pin "8") (pinfunction "Y4_8") (pintype "output"))
    )
    (net (code "118") (name "unconnected-(U6-Y5-Pad10)") (class "Default")
      (node (ref "U6") (pin "10") (pinfunction "Y5_10") (pintype "output"))
    )
    (net (code "119") (name "unconnected-(U6-Y6-Pad12)") (class "Default")
      (node (ref "U6") (pin "12") (pinfunction "Y6_12") (pintype "output"))
    )
    (net (code "120") (name "unconnected-(U7-A4-Pad12)") (class "Default")
      (node (ref "U7") (pin "12") (pinfunction "A4_12") (pintype "input"))
    )
    (net (code "121") (name "unconnected-(U7-B4-Pad13)") (class "Default")
      (node (ref "U7") (pin "13") (pinfunction "B4_13") (pintype "input"))
    )
    (net (code "122") (name "unconnected-(U7-Y4-Pad11)") (class "Default")
      (node (ref "U7") (pin "11") (pinfunction "Y4_11") (pintype "output"))
    )
    (net (code "123") (name "unconnected-(U11-INTA-Pad14)") (class "Default")
      (node (ref "U11") (pin "14") (pinfunction "INTA_14") (pintype "output"))
    )
    (net (code "124") (name "unconnected-(U11-INTB-Pad13)") (class "Default")
      (node (ref "U11") (pin "13") (pinfunction "INTB_13") (pintype "output"))
    )
    (net (code "125") (name "unconnected-(U25-GPB3-Pad3)") (class "Default")
      (node (ref "U25") (pin "3") (pinfunction "GPB3_3") (pintype "bidirectional"))
    )
    (net (code "126") (name "unconnected-(U25-GPB4-Pad4)") (class "Default")
      (node (ref "U25") (pin "4") (pinfunction "GPB4_4") (pintype "bidirectional"))
    )
    (net (code "127") (name "unconnected-(U25-GPB6-Pad6)") (class "Default")
      (node (ref "U25") (pin "6") (pinfunction "GPB6_6") (pintype "bidirectional"))
    )
    (net (code "128") (name "unconnected-(U25-GPB7-Pad7)") (class "Default")
      (node (ref "U25") (pin "7") (pinfunction "GPB7_7") (pintype "bidirectional"))
    )
    (net (code "129") (name "unconnected-(U26-GPA4-Pad19)") (class "Default")
      (node (ref "U26") (pin "19") (pinfunction "GPA4_19") (pintype "bidirectional"))
    )
    (net (code "130") (name "unconnected-(U26-GPA5-Pad20)") (class "Default")
      (node (ref "U26") (pin "20") (pinfunction "GPA5_20") (pintype "bidirectional"))
    )
    (net (code "131") (name "unconnected-(U26-GPA6-Pad21)") (class "Default")
      (node (ref "U26") (pin "21") (pinfunction "GPA6_21") (pintype "bidirectional"))
    )
    (net (code "132") (name "unconnected-(U26-GPA7-Pad22)") (class "Default")
      (node (ref "U26") (pin "22") (pinfunction "GPA7_22") (pintype "bidirectional"))
    )
    (net (code "133") (name "unconnected-(U26-GPB3-Pad3)") (class "Default")
      (node (ref "U26") (pin "3") (pinfunction "GPB3_3") (pintype "bidirectional"))
    )
    (net (code "134") (name "unconnected-(U26-GPB5-Pad5)") (class "Default")
      (node (ref "U26") (pin "5") (pinfunction "GPB5_5") (pintype "bidirectional"))
    )
    (net (code "135") (name "unconnected-(U26-GPB6-Pad6)") (class "Default")
      (node (ref "U26") (pin "6") (pinfunction "GPB6_6") (pintype "bidirectional"))
    )
    (net (code "136") (name "unconnected-(U26-GPB7-Pad7)") (class "Default")
      (node (ref "U26") (pin "7") (pinfunction "GPB7_7") (pintype "bidirectional"))
    )
    (net (code "137") (name "unconnected-(U26-INTA-Pad14)") (class "Default")
      (node (ref "U26") (pin "14") (pinfunction "INTA_14") (pintype "output"))
    )
    (net (code "138") (name "unconnected-(U26-INTB-Pad13)") (class "Default")
      (node (ref "U26") (pin "13") (pinfunction "INTB_13") (pintype "output"))
    )
    (net (code "139") (name "unconnected-(U32-A4-Pad6)") (class "Default")
      (node (ref "U32") (pin "6") (pinfunction "A4_6") (pintype "bidirectional"))
    )
    (net (code "140") (name "unconnected-(U32-B4-Pad9)") (class "Default")
      (node (ref "U32") (pin "9") (pinfunction "B4_9") (pintype "bidirectional"))
    )
    (net (code "141") (name "~{FAULT1}") (class "Default")
      (node (ref "U26") (pin "24") (pinfunction "GPB0_24") (pintype "bidirectional"))
      (node (ref "U5") (pin "13") (pinfunction "Q1_13") (pintype "output"))
      (node (ref "U6") (pin "1") (pinfunction "A1_1") (pintype "input"))
    )
    (net (code "142") (name "~{FAULT2}") (class "Default")
      (node (ref "U26") (pin "1") (pinfunction "GPB1_1") (pintype "bidirectional"))
      (node (ref "U5") (pin "9") (pinfunction "Q2_9") (pintype "output"))
      (node (ref "U6") (pin "3") (pinfunction "A2_3") (pintype "input"))
    )
    (net (code "143") (name "~{FAULT3}") (class "Default")
      (node (ref "U26") (pin "2") (pinfunction "GPB2_2") (pintype "bidirectional"))
      (node (ref "U5") (pin "10") (pinfunction "Q3_10") (pintype "output"))
      (node (ref "U6") (pin "5") (pinfunction "A3_5") (pintype "input"))
    )
    (net (code "144") (name "~{OVF1}") (class "Default")
      (node (ref "U10") (pin "9") (pinfunction "~{RCO}_9") (pintype "output"))
      (node (ref "U25") (pin "24") (pinfunction "GPB0_24") (pintype "bidirectional"))
    )
    (net (code "145") (name "~{OVF2}") (class "Default")
      (node (ref "U13") (pin "9") (pinfunction "~{RCO}_9") (pintype "output"))
      (node (ref "U25") (pin "1") (pinfunction "GPB1_1") (pintype "bidirectional"))
    )
    (net (code "146") (name "~{OVF3}") (class "Default")
      (node (ref "U15") (pin "9") (pinfunction "~{RCO}_9") (pintype "output"))
      (node (ref "U25") (pin "2") (pinfunction "GPB2_2") (pintype "bidirectional"))
    )
    (net (code "147") (name "~{RST}") (class "Default")
      (node (ref "U10") (pin "10") (pinfunction "~{CCLR}_10") (pintype "input"))
      (node (ref "U12") (pin "10") (pinfunction "~{CCLR}_10") (pintype "input"))
      (node (ref "U13") (pin "10") (pinfunction "~{CCLR}_10") (pintype "input"))
      (node (ref "U14") (pin "10") (pinfunction "~{CCLR}_10") (pintype "input"))
      (node (ref "U15") (pin "10") (pinfunction "~{CCLR}_10") (pintype "input"))
      (node (ref "U25") (pin "21") (pinfunction "GPA6_21") (pintype "bidirectional"))
      (node (ref "U9") (pin "10") (pinfunction "~{CCLR}_10") (pintype "input"))
    )
  )
)
